# InteractionBoard.net
KiCad netlist of a schematic drawn in EAGLE
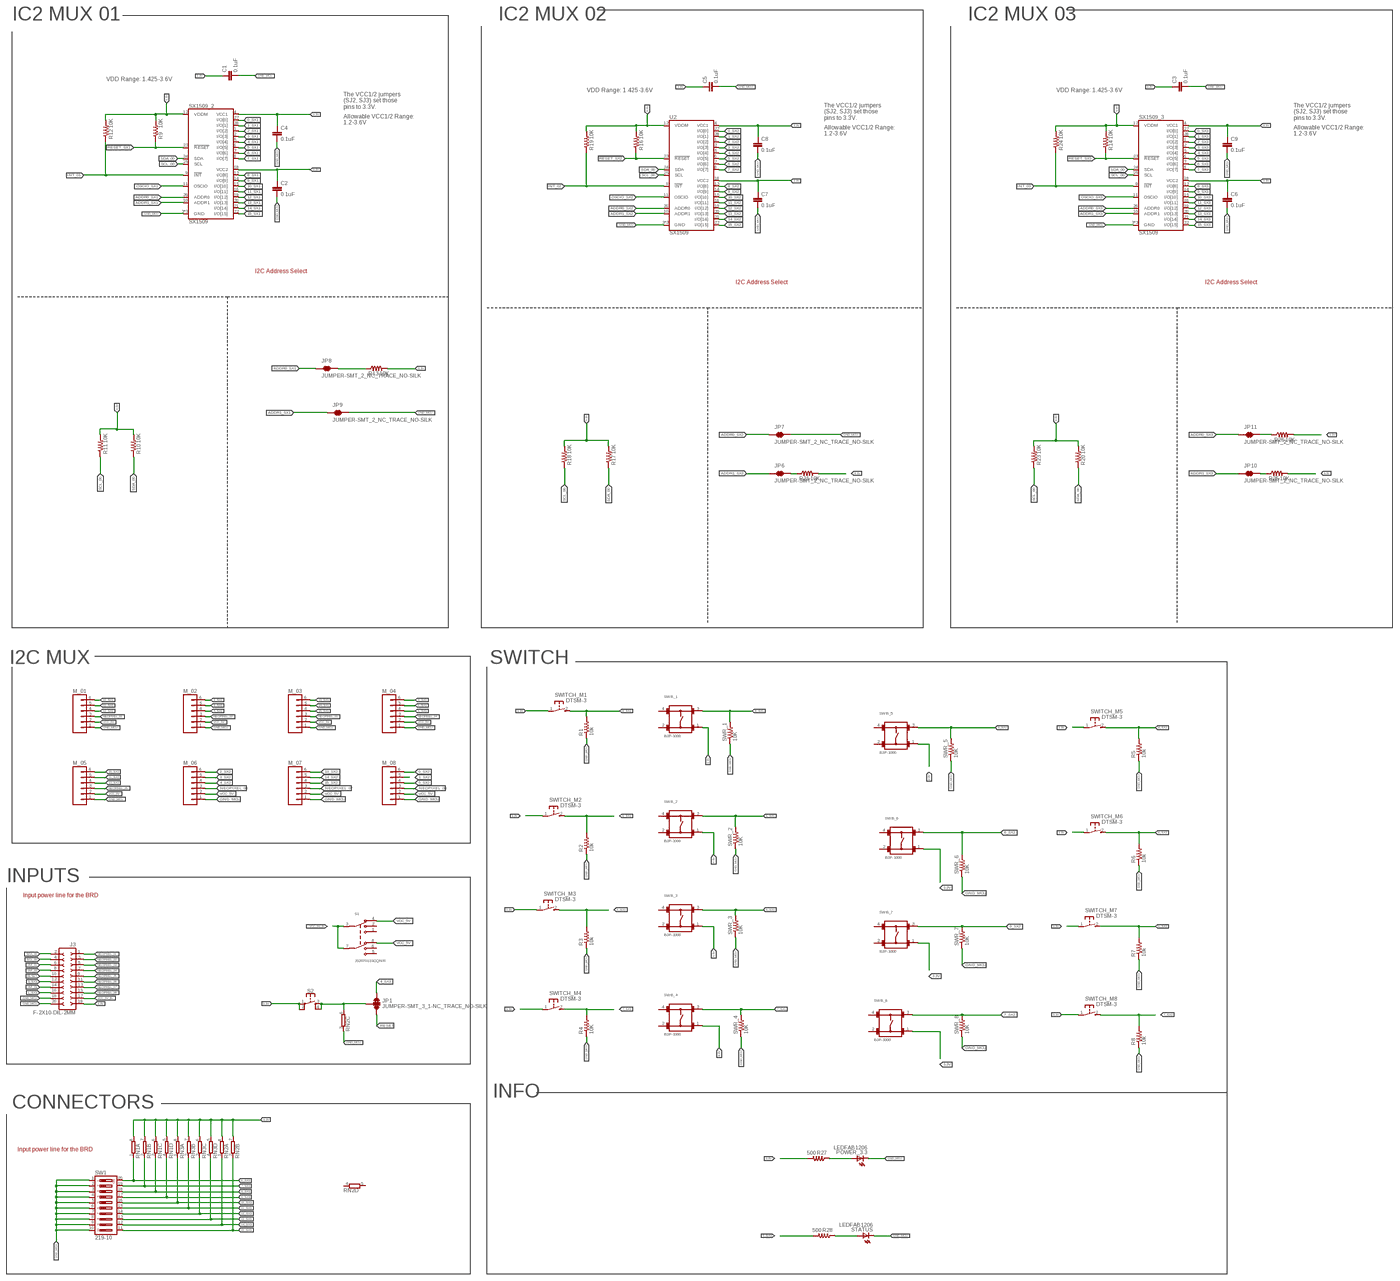
[diagram p0: schematic, sheet 1, overview]
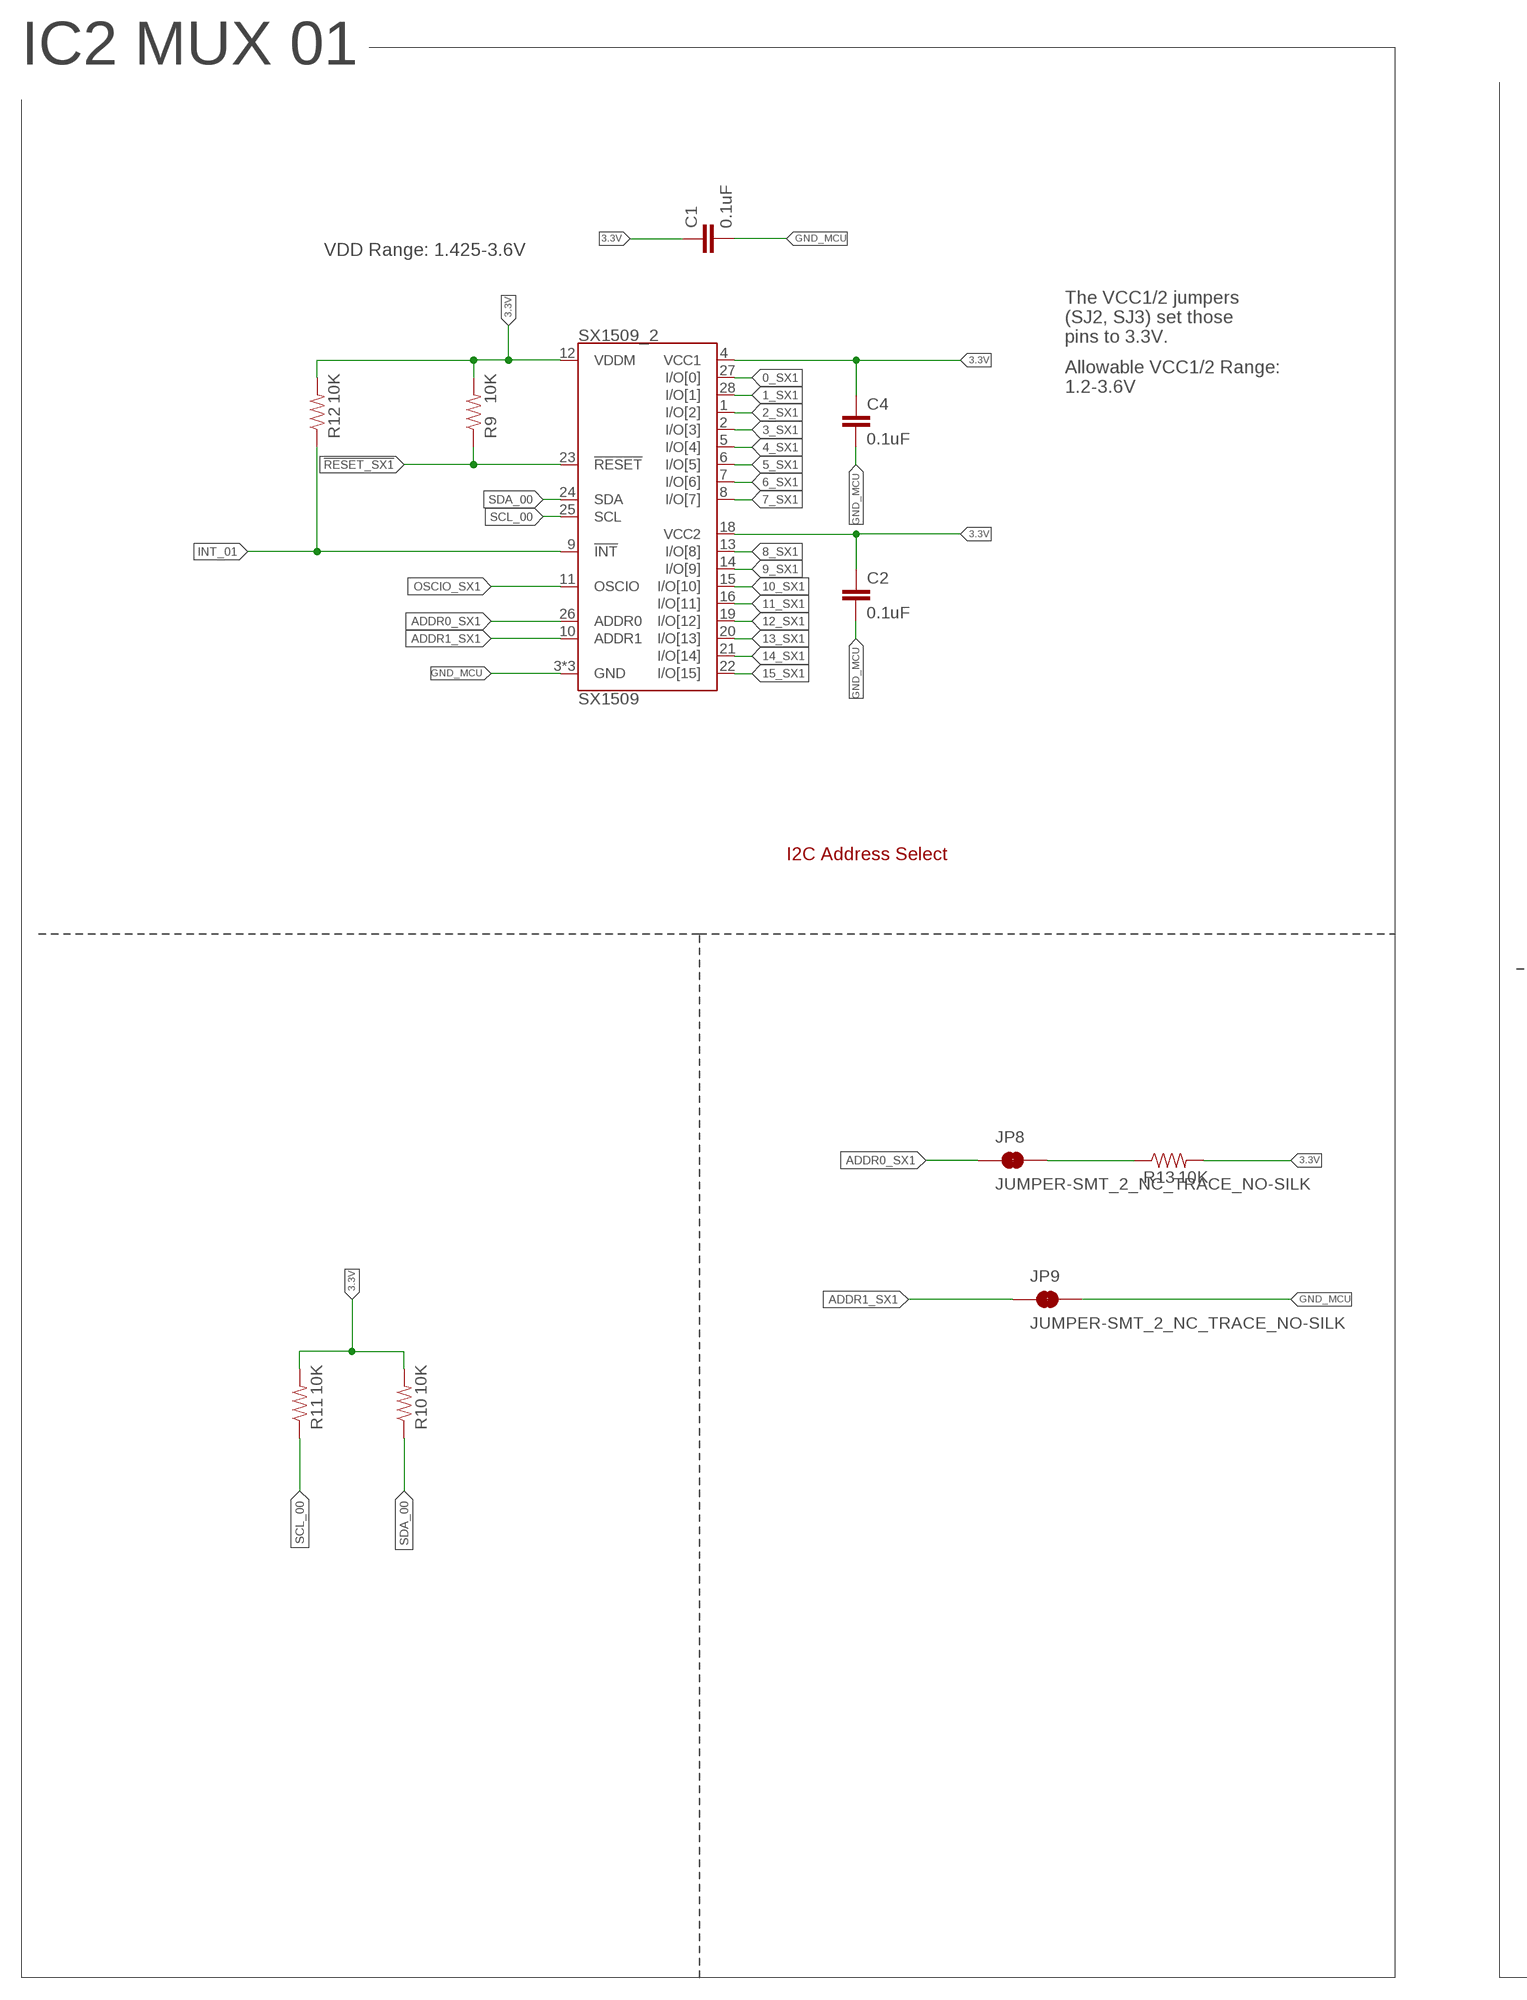
[diagram p1: schematic, sheet 1, part 1 of 4]
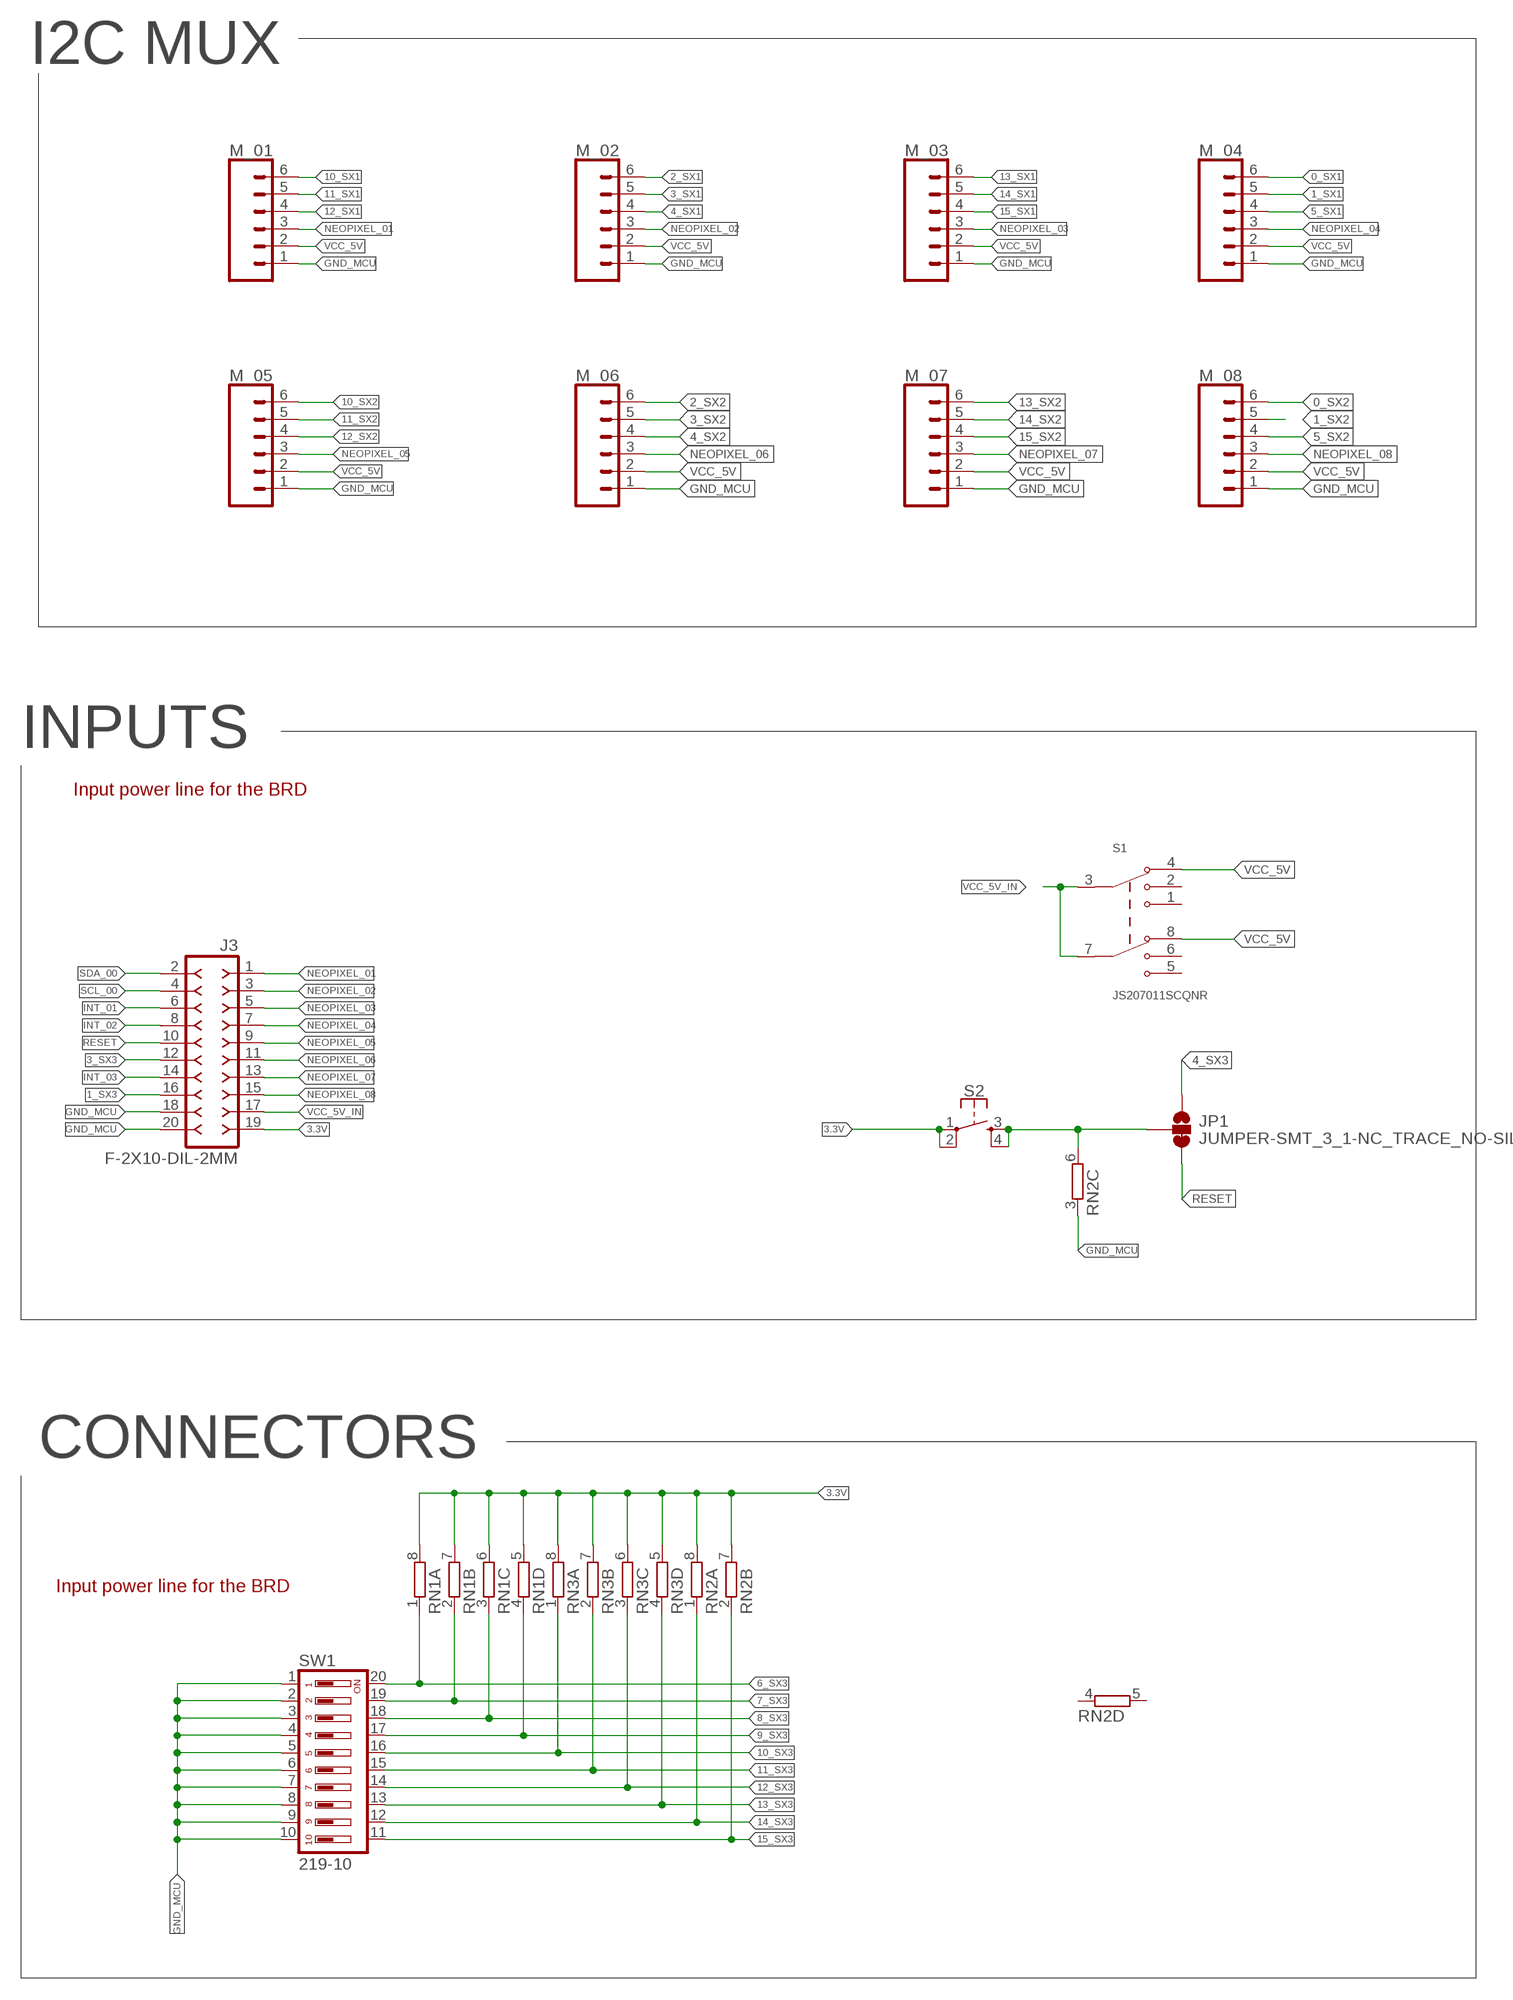
[diagram p2: schematic, sheet 1, part 2 of 4]
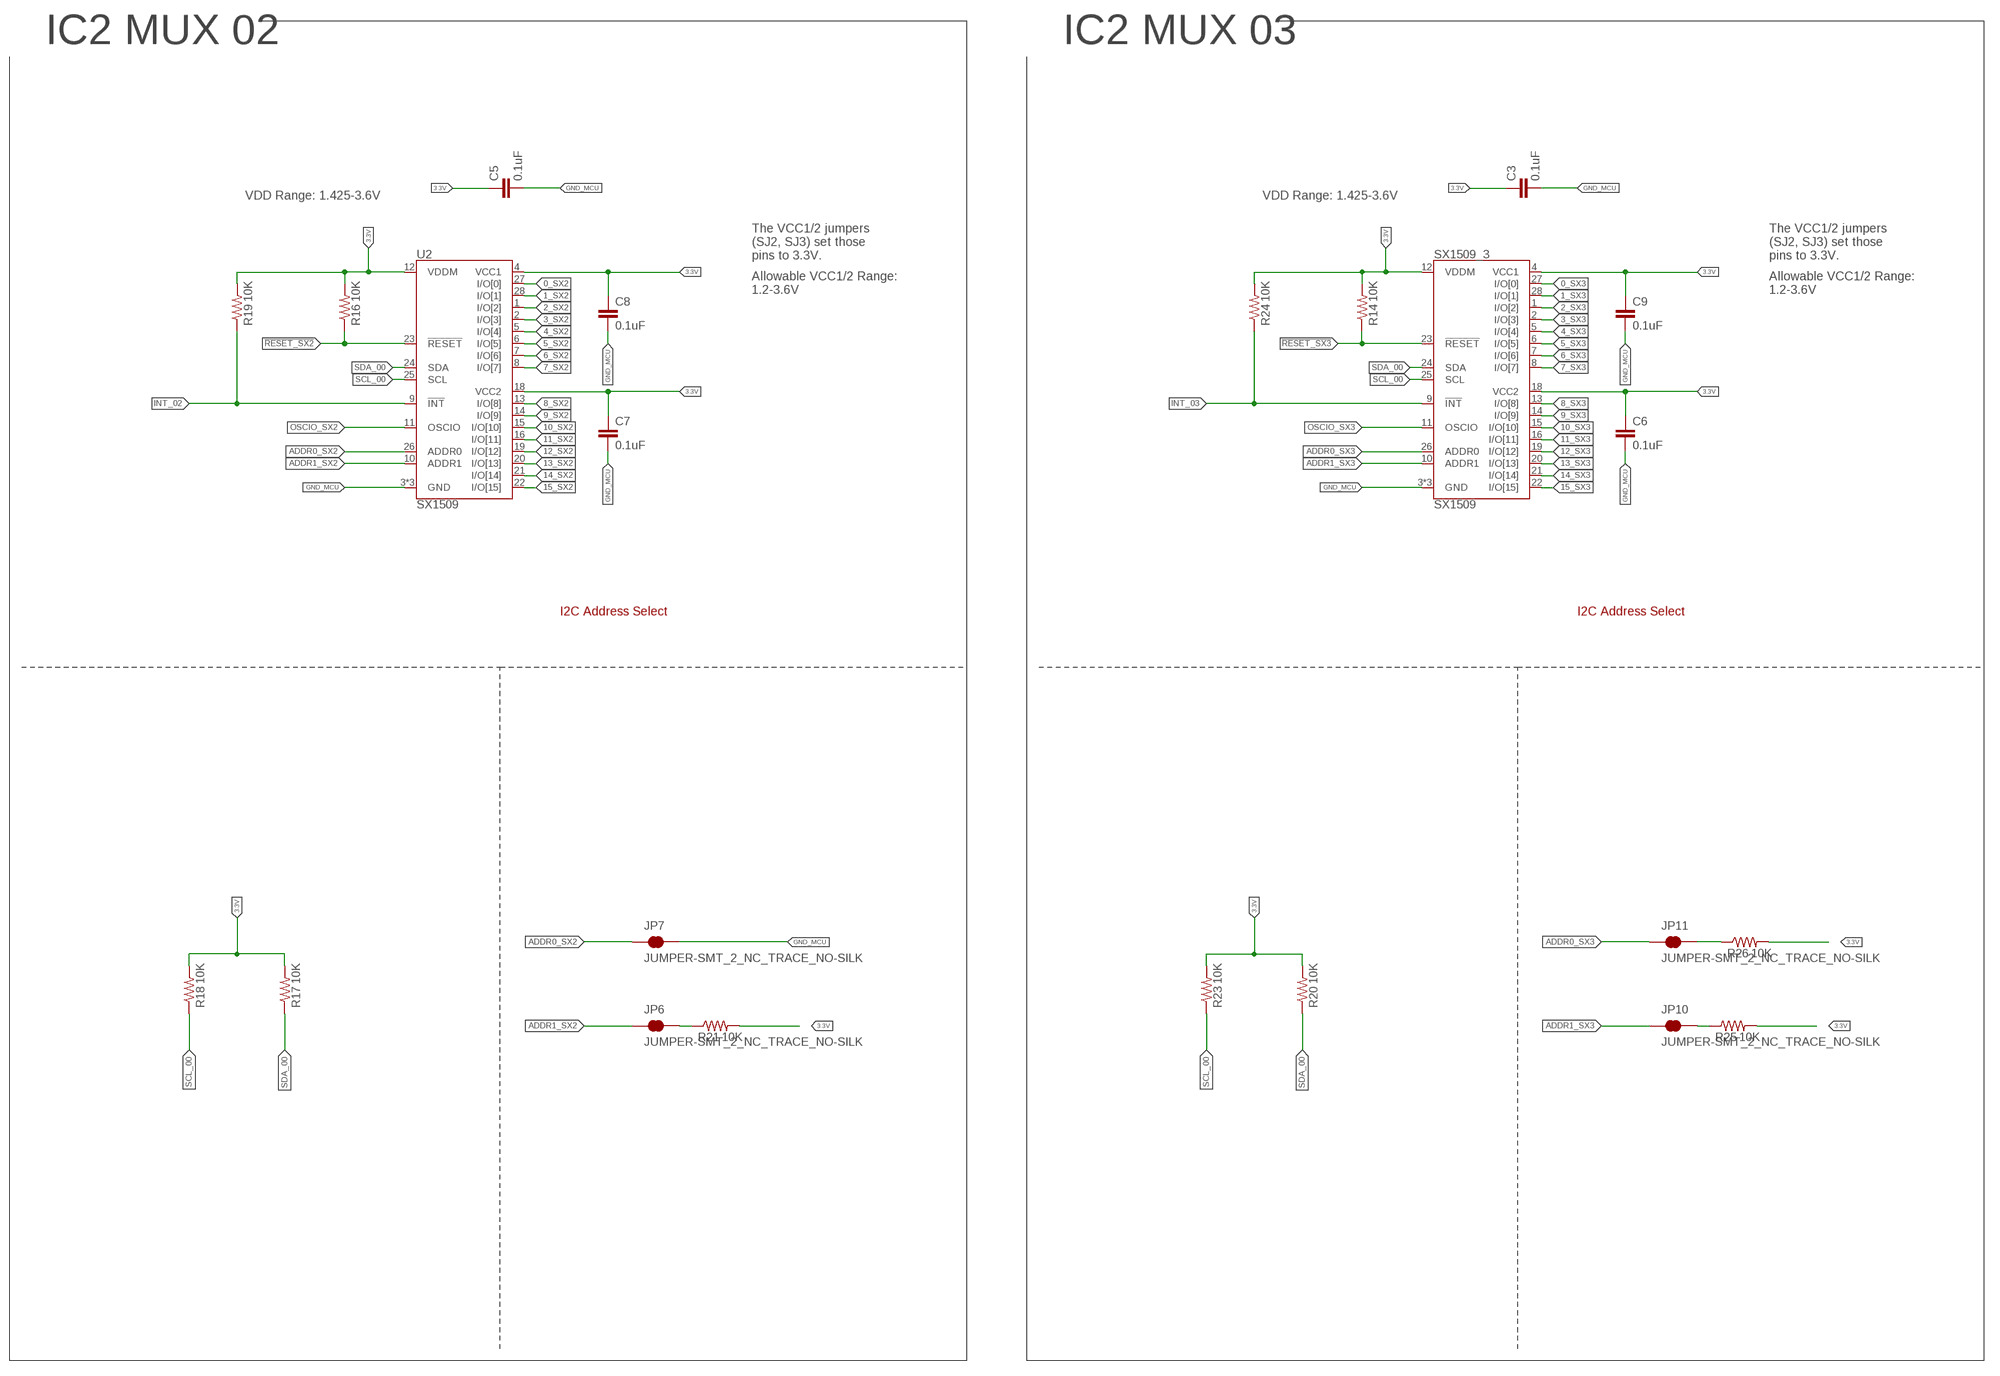
[diagram p3: schematic, sheet 1, part 3 of 4]
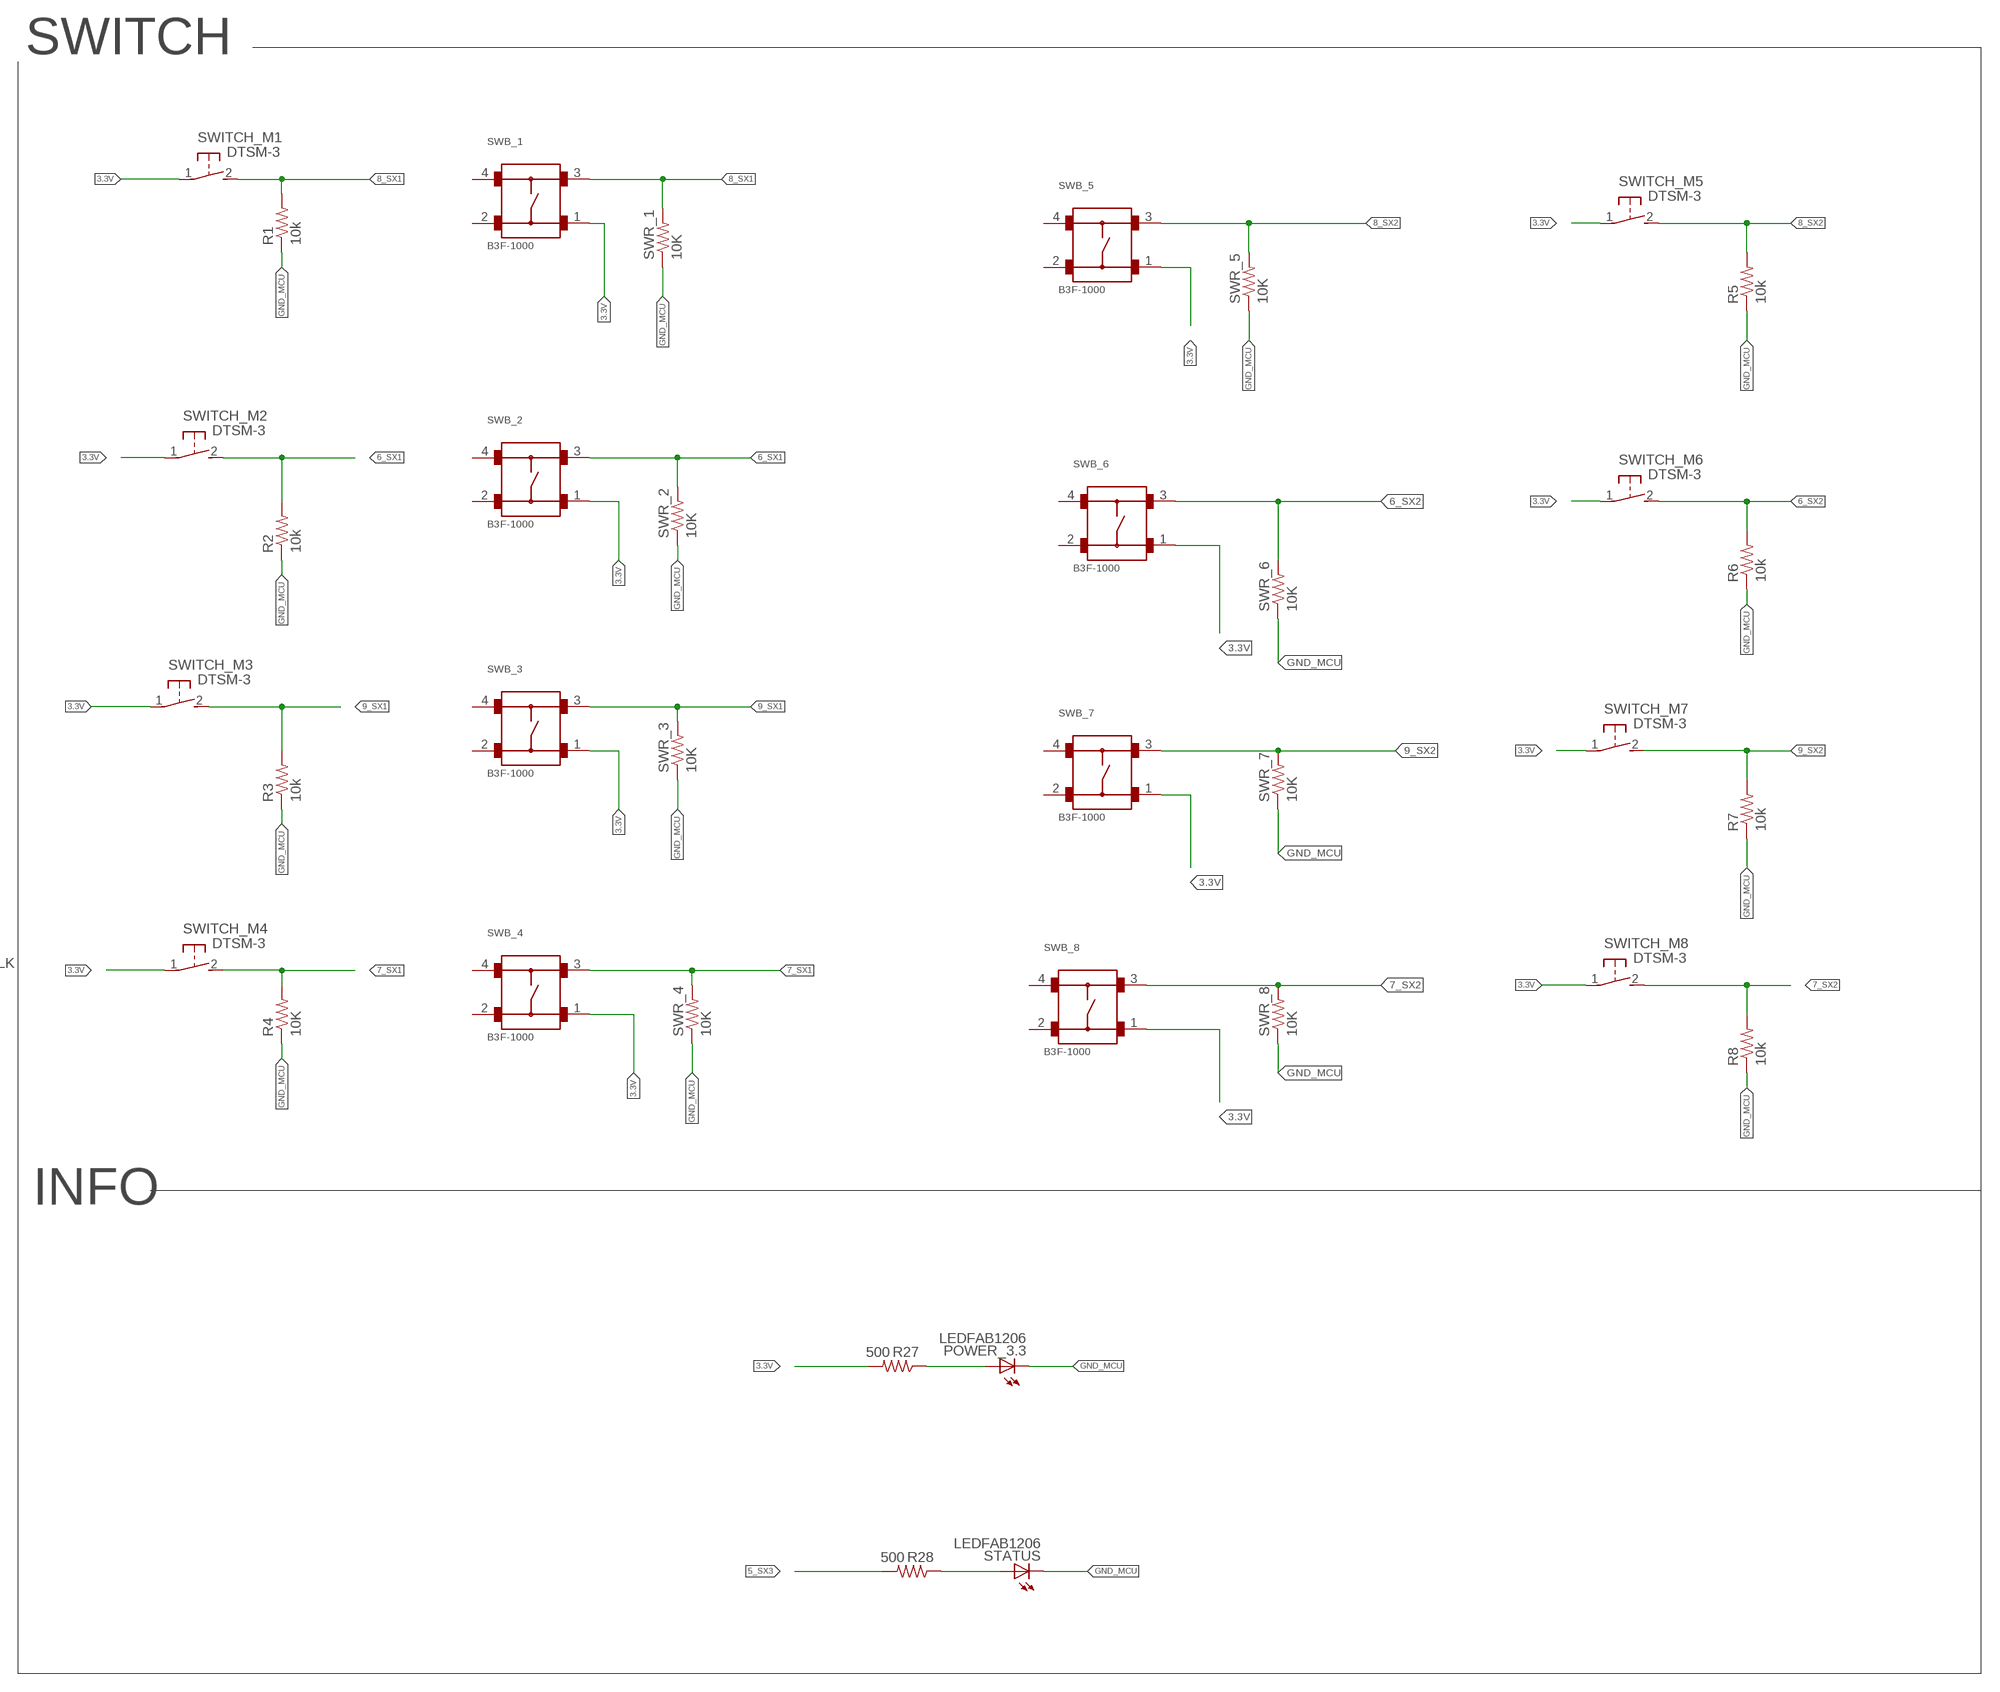
[diagram p4: schematic, sheet 1, part 4 of 4]

(export (version "E")
  (design (tool "Eeschema 10.0.6"))
  (components
    (comp (ref "C1")
      (value "0.1uF")
      (footprint "eagle-import:0603-CAP")
      (libsource (lib "eagle-import") (part "0.1UF-25V(+80/-20%)(0603)"))
    )
    (comp (ref "C2")
      (value "0.1uF")
      (footprint "eagle-import:0603-CAP")
      (libsource (lib "eagle-import") (part "0.1UF-25V(+80/-20%)(0603)"))
    )
    (comp (ref "C3")
      (value "0.1uF")
      (footprint "eagle-import:0603-CAP")
      (libsource (lib "eagle-import") (part "0.1UF-25V(+80/-20%)(0603)"))
    )
    (comp (ref "C4")
      (value "0.1uF")
      (footprint "eagle-import:0603-CAP")
      (libsource (lib "eagle-import") (part "0.1UF-25V(+80/-20%)(0603)"))
    )
    (comp (ref "C5")
      (value "0.1uF")
      (footprint "eagle-import:0603-CAP")
      (libsource (lib "eagle-import") (part "0.1UF-25V(+80/-20%)(0603)"))
    )
    (comp (ref "C6")
      (value "0.1uF")
      (footprint "eagle-import:0603-CAP")
      (libsource (lib "eagle-import") (part "0.1UF-25V(+80/-20%)(0603)"))
    )
    (comp (ref "C7")
      (value "0.1uF")
      (footprint "eagle-import:0603-CAP")
      (libsource (lib "eagle-import") (part "0.1UF-25V(+80/-20%)(0603)"))
    )
    (comp (ref "C8")
      (value "0.1uF")
      (footprint "eagle-import:0603-CAP")
      (libsource (lib "eagle-import") (part "0.1UF-25V(+80/-20%)(0603)"))
    )
    (comp (ref "C9")
      (value "0.1uF")
      (footprint "eagle-import:0603-CAP")
      (libsource (lib "eagle-import") (part "0.1UF-25V(+80/-20%)(0603)"))
    )
    (comp (ref "J3")
      (value "F-2X10-DIL-2MM")
      (footprint "eagle-import:DIL-2MM-2X10")
      (libsource (lib "eagle-import") (part "F-2X10-DIL-2MM"))
    )
    (comp (ref "JP1")
      (value "JUMPER-SMT_3_1-NC_TRACE_NO-SILK")
      (footprint "eagle-import:SMT-JUMPER_3_1-NC_TRACE_NO-SILK")
      (libsource (lib "eagle-import") (part "JUMPER-SMT_3_1-NC_TRACE_NO-SILK"))
    )
    (comp (ref "JP6")
      (value "JUMPER-SMT_2_NC_TRACE_NO-SILK")
      (footprint "eagle-import:SMT-JUMPER_2_NC_TRACE_NO-SILK")
      (libsource (lib "eagle-import") (part "JUMPER-SMT_2_NC_TRACE_NO-SILK"))
    )
    (comp (ref "JP7")
      (value "JUMPER-SMT_2_NC_TRACE_NO-SILK")
      (footprint "eagle-import:SMT-JUMPER_2_NC_TRACE_NO-SILK")
      (libsource (lib "eagle-import") (part "JUMPER-SMT_2_NC_TRACE_NO-SILK"))
    )
    (comp (ref "JP8")
      (value "JUMPER-SMT_2_NC_TRACE_NO-SILK")
      (footprint "eagle-import:SMT-JUMPER_2_NC_TRACE_NO-SILK")
      (libsource (lib "eagle-import") (part "JUMPER-SMT_2_NC_TRACE_NO-SILK"))
    )
    (comp (ref "JP9")
      (value "JUMPER-SMT_2_NC_TRACE_NO-SILK")
      (footprint "eagle-import:SMT-JUMPER_2_NC_TRACE_NO-SILK")
      (libsource (lib "eagle-import") (part "JUMPER-SMT_2_NC_TRACE_NO-SILK"))
    )
    (comp (ref "JP10")
      (value "JUMPER-SMT_2_NC_TRACE_NO-SILK")
      (footprint "eagle-import:SMT-JUMPER_2_NC_TRACE_NO-SILK")
      (libsource (lib "eagle-import") (part "JUMPER-SMT_2_NC_TRACE_NO-SILK"))
    )
    (comp (ref "JP11")
      (value "JUMPER-SMT_2_NC_TRACE_NO-SILK")
      (footprint "eagle-import:SMT-JUMPER_2_NC_TRACE_NO-SILK")
      (libsource (lib "eagle-import") (part "JUMPER-SMT_2_NC_TRACE_NO-SILK"))
    )
    (comp (ref "M_01")
      (value "CONN_06SMD-1MM")
      (footprint "eagle-import:1X06-1MM")
      (libsource (lib "eagle-import") (part "CONN_06SMD-1MM"))
    )
    (comp (ref "M_02")
      (value "CONN_06SMD-1MM")
      (footprint "eagle-import:1X06-1MM")
      (libsource (lib "eagle-import") (part "CONN_06SMD-1MM"))
    )
    (comp (ref "M_03")
      (value "CONN_06SMD-1MM")
      (footprint "eagle-import:1X06-1MM")
      (libsource (lib "eagle-import") (part "CONN_06SMD-1MM"))
    )
    (comp (ref "M_04")
      (value "CONN_06SMD-1MM")
      (footprint "eagle-import:1X06-1MM")
      (libsource (lib "eagle-import") (part "CONN_06SMD-1MM"))
    )
    (comp (ref "M_05")
      (value "CONN_06SMD-1MM")
      (footprint "eagle-import:1X06-1MM")
      (libsource (lib "eagle-import") (part "CONN_06SMD-1MM"))
    )
    (comp (ref "M_06")
      (value "CONN_06SMD-1MM")
      (footprint "eagle-import:1X06-1MM")
      (libsource (lib "eagle-import") (part "CONN_06SMD-1MM"))
    )
    (comp (ref "M_07")
      (value "CONN_06SMD-1MM")
      (footprint "eagle-import:1X06-1MM")
      (libsource (lib "eagle-import") (part "CONN_06SMD-1MM"))
    )
    (comp (ref "M_08")
      (value "CONN_06SMD-1MM")
      (footprint "eagle-import:1X06-1MM")
      (libsource (lib "eagle-import") (part "CONN_06SMD-1MM"))
    )
    (comp (ref "POWER_3.3")
      (value "LEDFAB1206")
      (footprint "eagle-import:LED1206FAB")
      (libsource (lib "eagle-import") (part "LEDFAB1206"))
    )
    (comp (ref "R1")
      (value "10k")
      (footprint "eagle-import:M0805")
      (libsource (lib "eagle-import") (part "R-US_M0805"))
    )
    (comp (ref "R2")
      (value "10k")
      (footprint "eagle-import:M0805")
      (libsource (lib "eagle-import") (part "R-US_M0805"))
    )
    (comp (ref "R3")
      (value "10k")
      (footprint "eagle-import:M0805")
      (libsource (lib "eagle-import") (part "R-US_M0805"))
    )
    (comp (ref "R4")
      (value "10K")
      (footprint "eagle-import:M0805")
      (libsource (lib "eagle-import") (part "R-US_M0805"))
    )
    (comp (ref "R5")
      (value "10k")
      (footprint "eagle-import:M0805")
      (libsource (lib "eagle-import") (part "R-US_M0805"))
    )
    (comp (ref "R6")
      (value "10k")
      (footprint "eagle-import:M0805")
      (libsource (lib "eagle-import") (part "R-US_M0805"))
    )
    (comp (ref "R7")
      (value "10k")
      (footprint "eagle-import:M0805")
      (libsource (lib "eagle-import") (part "R-US_M0805"))
    )
    (comp (ref "R8")
      (value "10k")
      (footprint "eagle-import:M0805")
      (libsource (lib "eagle-import") (part "R-US_M0805"))
    )
    (comp (ref "R9")
      (value "10K")
      (footprint "eagle-import:0603-RES")
      (libsource (lib "eagle-import") (part "SparkFun-Resistors_532_10KOHM-1/10W-1%(0603)0603"))
    )
    (comp (ref "R10")
      (value "10K")
      (footprint "eagle-import:0603-RES")
      (libsource (lib "eagle-import") (part "SparkFun-Resistors_532_10KOHM-1/10W-1%(0603)0603"))
    )
    (comp (ref "R11")
      (value "10K")
      (footprint "eagle-import:0603-RES")
      (libsource (lib "eagle-import") (part "SparkFun-Resistors_532_10KOHM-1/10W-1%(0603)0603"))
    )
    (comp (ref "R12")
      (value "10K")
      (footprint "eagle-import:0603-RES")
      (libsource (lib "eagle-import") (part "SparkFun-Resistors_532_10KOHM-1/10W-1%(0603)0603"))
    )
    (comp (ref "R13")
      (value "10K")
      (footprint "eagle-import:0603-RES")
      (libsource (lib "eagle-import") (part "SparkFun-Resistors_532_10KOHM-1/10W-1%(0603)0603"))
    )
    (comp (ref "R14")
      (value "10K")
      (footprint "eagle-import:0603-RES")
      (libsource (lib "eagle-import") (part "SparkFun-Resistors_532_10KOHM-1/10W-1%(0603)0603"))
    )
    (comp (ref "R16")
      (value "10K")
      (footprint "eagle-import:0603-RES")
      (libsource (lib "eagle-import") (part "SparkFun-Resistors_532_10KOHM-1/10W-1%(0603)0603"))
    )
    (comp (ref "R17")
      (value "10K")
      (footprint "eagle-import:0603-RES")
      (libsource (lib "eagle-import") (part "SparkFun-Resistors_532_10KOHM-1/10W-1%(0603)0603"))
    )
    (comp (ref "R18")
      (value "10K")
      (footprint "eagle-import:0603-RES")
      (libsource (lib "eagle-import") (part "SparkFun-Resistors_532_10KOHM-1/10W-1%(0603)0603"))
    )
    (comp (ref "R19")
      (value "10K")
      (footprint "eagle-import:0603-RES")
      (libsource (lib "eagle-import") (part "SparkFun-Resistors_532_10KOHM-1/10W-1%(0603)0603"))
    )
    (comp (ref "R20")
      (value "10K")
      (footprint "eagle-import:0603-RES")
      (libsource (lib "eagle-import") (part "SparkFun-Resistors_532_10KOHM-1/10W-1%(0603)0603"))
    )
    (comp (ref "R21")
      (value "10K")
      (footprint "eagle-import:0603-RES")
      (libsource (lib "eagle-import") (part "SparkFun-Resistors_532_10KOHM-1/10W-1%(0603)0603"))
    )
    (comp (ref "R23")
      (value "10K")
      (footprint "eagle-import:0603-RES")
      (libsource (lib "eagle-import") (part "SparkFun-Resistors_532_10KOHM-1/10W-1%(0603)0603"))
    )
    (comp (ref "R24")
      (value "10K")
      (footprint "eagle-import:0603-RES")
      (libsource (lib "eagle-import") (part "SparkFun-Resistors_532_10KOHM-1/10W-1%(0603)0603"))
    )
    (comp (ref "R25")
      (value "10K")
      (footprint "eagle-import:0603-RES")
      (libsource (lib "eagle-import") (part "SparkFun-Resistors_532_10KOHM-1/10W-1%(0603)0603"))
    )
    (comp (ref "R26")
      (value "10K")
      (footprint "eagle-import:0603-RES")
      (libsource (lib "eagle-import") (part "SparkFun-Resistors_532_10KOHM-1/10W-1%(0603)0603"))
    )
    (comp (ref "R27")
      (value "500")
      (footprint "eagle-import:0603-RES")
      (libsource (lib "eagle-import") (part "10KOHM-1/10W-1%(0603)0603"))
    )
    (comp (ref "R28")
      (value "500")
      (footprint "eagle-import:0603-RES")
      (libsource (lib "eagle-import") (part "10KOHM-1/10W-1%(0603)0603"))
    )
    (comp (ref "RN1")
      (value "4R-NEXB38V")
      (footprint "eagle-import:EXB38V")
      (libsource (lib "eagle-import") (part "4R-NEXB38V"))
    )
    (comp (ref "RN2")
      (value "4R-NEXB38V")
      (footprint "eagle-import:EXB38V")
      (libsource (lib "eagle-import") (part "4R-NEXB38V"))
    )
    (comp (ref "RN3")
      (value "4R-NEXB38V")
      (footprint "eagle-import:EXB38V")
      (libsource (lib "eagle-import") (part "4R-NEXB38V"))
    )
    (comp (ref "S1")
      (value "JS207011SCQNR")
      (footprint "eagle-import:SW_JS207011SCQNR")
      (fields (field (name "MF") "C&K"))
      (libsource (lib "eagle-import") (part "JS207011SCQNR"))
    )
    (comp (ref "S2")
      (value "MOMENTARY-SWITCH-SPST-2-SMD-5.2MM")
      (footprint "eagle-import:TACTILE_SWITCH_SMD_5.2MM")
      (libsource (lib "eagle-import") (part "MOMENTARY-SWITCH-SPST-2-SMD-5.2MM"))
    )
    (comp (ref "STATUS")
      (value "LEDFAB1206")
      (footprint "eagle-import:LED1206FAB")
      (libsource (lib "eagle-import") (part "LEDFAB1206"))
    )
    (comp (ref "SW1")
      (value "219-10")
      (footprint "eagle-import:CTS-219-10")
      (fields (field (name "MF") "SLI (CML/IDI)") (field (name "MPN") "219-10PK"))
      (libsource (lib "eagle-import") (part "219-10"))
    )
    (comp (ref "SWB_1")
      (value "B3F-1000")
      (footprint "eagle-import:B3F-1000")
      (fields
        (field (name "DIGI_KEY_PART_NUMBER") "SW400-ND")
        (field (name "MANUFACTURER") "Omron Electronics Inc-EMC Div")
        (field (name "CREATED_BY") "PCBLayout.com")
      )
      (libsource (lib "eagle-import") (part "B3F-1000"))
    )
    (comp (ref "SWB_2")
      (value "B3F-1000")
      (footprint "eagle-import:B3F-1000")
      (fields
        (field (name "DIGI_KEY_PART_NUMBER") "SW400-ND")
        (field (name "MANUFACTURER") "Omron Electronics Inc-EMC Div")
        (field (name "CREATED_BY") "PCBLayout.com")
      )
      (libsource (lib "eagle-import") (part "B3F-1000"))
    )
    (comp (ref "SWB_3")
      (value "B3F-1000")
      (footprint "eagle-import:B3F-1000")
      (fields
        (field (name "DIGI_KEY_PART_NUMBER") "SW400-ND")
        (field (name "MANUFACTURER") "Omron Electronics Inc-EMC Div")
        (field (name "CREATED_BY") "PCBLayout.com")
      )
      (libsource (lib "eagle-import") (part "B3F-1000"))
    )
    (comp (ref "SWB_4")
      (value "B3F-1000")
      (footprint "eagle-import:B3F-1000")
      (fields
        (field (name "DIGI_KEY_PART_NUMBER") "SW400-ND")
        (field (name "MANUFACTURER") "Omron Electronics Inc-EMC Div")
        (field (name "CREATED_BY") "PCBLayout.com")
      )
      (libsource (lib "eagle-import") (part "B3F-1000"))
    )
    (comp (ref "SWB_5")
      (value "B3F-1000")
      (footprint "eagle-import:B3F-1000")
      (fields
        (field (name "DIGI_KEY_PART_NUMBER") "SW400-ND")
        (field (name "MANUFACTURER") "Omron Electronics Inc-EMC Div")
        (field (name "CREATED_BY") "PCBLayout.com")
      )
      (libsource (lib "eagle-import") (part "B3F-1000"))
    )
    (comp (ref "SWB_6")
      (value "B3F-1000")
      (footprint "eagle-import:B3F-1000")
      (fields
        (field (name "DIGI_KEY_PART_NUMBER") "SW400-ND")
        (field (name "MANUFACTURER") "Omron Electronics Inc-EMC Div")
        (field (name "CREATED_BY") "PCBLayout.com")
      )
      (libsource (lib "eagle-import") (part "B3F-1000"))
    )
    (comp (ref "SWB_7")
      (value "B3F-1000")
      (footprint "eagle-import:B3F-1000")
      (fields
        (field (name "DIGI_KEY_PART_NUMBER") "SW400-ND")
        (field (name "MANUFACTURER") "Omron Electronics Inc-EMC Div")
        (field (name "CREATED_BY") "PCBLayout.com")
      )
      (libsource (lib "eagle-import") (part "B3F-1000"))
    )
    (comp (ref "SWB_8")
      (value "B3F-1000")
      (footprint "eagle-import:B3F-1000")
      (fields
        (field (name "DIGI_KEY_PART_NUMBER") "SW400-ND")
        (field (name "MANUFACTURER") "Omron Electronics Inc-EMC Div")
        (field (name "CREATED_BY") "PCBLayout.com")
      )
      (libsource (lib "eagle-import") (part "B3F-1000"))
    )
    (comp (ref "SWITCH_M1")
      (value "DTSM-3")
      (footprint "eagle-import:DTSM-3")
      (libsource (lib "eagle-import") (part "DTSM-3"))
    )
    (comp (ref "SWITCH_M2")
      (value "DTSM-3")
      (footprint "eagle-import:DTSM-3")
      (libsource (lib "eagle-import") (part "DTSM-3"))
    )
    (comp (ref "SWITCH_M3")
      (value "DTSM-3")
      (footprint "eagle-import:DTSM-3")
      (libsource (lib "eagle-import") (part "DTSM-3"))
    )
    (comp (ref "SWITCH_M4")
      (value "DTSM-3")
      (footprint "eagle-import:DTSM-3")
      (libsource (lib "eagle-import") (part "DTSM-3"))
    )
    (comp (ref "SWITCH_M5")
      (value "DTSM-3")
      (footprint "eagle-import:DTSM-3")
      (libsource (lib "eagle-import") (part "DTSM-3"))
    )
    (comp (ref "SWITCH_M6")
      (value "DTSM-3")
      (footprint "eagle-import:DTSM-3")
      (libsource (lib "eagle-import") (part "DTSM-3"))
    )
    (comp (ref "SWITCH_M7")
      (value "DTSM-3")
      (footprint "eagle-import:DTSM-3")
      (libsource (lib "eagle-import") (part "DTSM-3"))
    )
    (comp (ref "SWITCH_M8")
      (value "DTSM-3")
      (footprint "eagle-import:DTSM-3")
      (libsource (lib "eagle-import") (part "DTSM-3"))
    )
    (comp (ref "SWR_1")
      (value "10K")
      (footprint "eagle-import:M0805")
      (libsource (lib "eagle-import") (part "R-US_M0805"))
    )
    (comp (ref "SWR_2")
      (value "10K")
      (footprint "eagle-import:M0805")
      (libsource (lib "eagle-import") (part "R-US_M0805"))
    )
    (comp (ref "SWR_3")
      (value "10K")
      (footprint "eagle-import:M0805")
      (libsource (lib "eagle-import") (part "R-US_M0805"))
    )
    (comp (ref "SWR_4")
      (value "10K")
      (footprint "eagle-import:M0805")
      (libsource (lib "eagle-import") (part "R-US_M0805"))
    )
    (comp (ref "SWR_5")
      (value "10K")
      (footprint "eagle-import:M0805")
      (libsource (lib "eagle-import") (part "R-US_M0805"))
    )
    (comp (ref "SWR_6")
      (value "10K")
      (footprint "eagle-import:M0805")
      (libsource (lib "eagle-import") (part "R-US_M0805"))
    )
    (comp (ref "SWR_7")
      (value "10K")
      (footprint "eagle-import:M0805")
      (libsource (lib "eagle-import") (part "R-US_M0805"))
    )
    (comp (ref "SWR_8")
      (value "10K")
      (footprint "eagle-import:M0805")
      (libsource (lib "eagle-import") (part "R-US_M0805"))
    )
    (comp (ref "SX1509_2")
      (value "SX1509")
      (footprint "eagle-import:QFN-28")
      (libsource (lib "eagle-import") (part "SX1509"))
    )
    (comp (ref "SX1509_3")
      (value "SX1509")
      (footprint "eagle-import:QFN-28")
      (libsource (lib "eagle-import") (part "SX1509"))
    )
    (comp (ref "U2")
      (value "SX1509")
      (footprint "eagle-import:QFN-28")
      (libsource (lib "eagle-import") (part "SX1509"))
    )
  )
  (nets
    (net (code "1") (name "/~{RESET_SX1}") (class "Default")
      (node (ref "R9") (pin "1") (pinfunction "1_1") (pintype "passive"))
      (node (ref "SX1509_2") (pin "23") (pinfunction "~{RESET}_23") (pintype "bidirectional"))
    )
    (net (code "2") (name "/~{RESET_SX2}") (class "Default")
      (node (ref "R16") (pin "1") (pinfunction "1_1") (pintype "passive"))
      (node (ref "U2") (pin "23") (pinfunction "~{RESET}_23") (pintype "bidirectional"))
    )
    (net (code "3") (name "/~{RESET_SX3}") (class "Default")
      (node (ref "R14") (pin "1") (pinfunction "1_1") (pintype "passive"))
      (node (ref "SX1509_3") (pin "23") (pinfunction "~{RESET}_23") (pintype "bidirectional"))
    )
    (net (code "4") (name "0_SX1") (class "Default")
      (node (ref "M_04") (pin "6") (pinfunction "6_6") (pintype "passive"))
      (node (ref "SX1509_2") (pin "27") (pinfunction "I/O[0]_27") (pintype "bidirectional"))
    )
    (net (code "5") (name "0_SX2") (class "Default")
      (node (ref "M_08") (pin "6") (pinfunction "6_6") (pintype "passive"))
      (node (ref "U2") (pin "27") (pinfunction "I/O[0]_27") (pintype "bidirectional"))
    )
    (net (code "6") (name "0_SX3") (class "Default")
      (node (ref "SX1509_3") (pin "27") (pinfunction "I/O[0]_27") (pintype "bidirectional"))
    )
    (net (code "7") (name "1_SX1") (class "Default")
      (node (ref "M_04") (pin "5") (pinfunction "5_5") (pintype "passive"))
      (node (ref "SX1509_2") (pin "28") (pinfunction "I/O[1]_28") (pintype "bidirectional"))
    )
    (net (code "8") (name "1_SX2") (class "Default")
      (node (ref "M_08") (pin "5") (pinfunction "5_5") (pintype "passive"))
      (node (ref "U2") (pin "28") (pinfunction "I/O[1]_28") (pintype "bidirectional"))
    )
    (net (code "9") (name "1_SX3") (class "Default")
      (node (ref "J3") (pin "16") (pinfunction "16_16") (pintype "passive"))
      (node (ref "SX1509_3") (pin "28") (pinfunction "I/O[1]_28") (pintype "bidirectional"))
    )
    (net (code "10") (name "2_SX1") (class "Default")
      (node (ref "M_02") (pin "6") (pinfunction "6_6") (pintype "passive"))
      (node (ref "SX1509_2") (pin "1") (pinfunction "I/O[2]_1") (pintype "bidirectional"))
    )
    (net (code "11") (name "2_SX2") (class "Default")
      (node (ref "M_06") (pin "6") (pinfunction "6_6") (pintype "passive"))
      (node (ref "U2") (pin "1") (pinfunction "I/O[2]_1") (pintype "bidirectional"))
    )
    (net (code "12") (name "2_SX3") (class "Default")
      (node (ref "SX1509_3") (pin "1") (pinfunction "I/O[2]_1") (pintype "bidirectional"))
    )
    (net (code "13") (name "3.3V") (class "Default")
      (node (ref "C1") (pin "1") (pinfunction "1_1") (pintype "passive"))
      (node (ref "C2") (pin "1") (pinfunction "1_1") (pintype "passive"))
      (node (ref "C3") (pin "1") (pinfunction "1_1") (pintype "passive"))
      (node (ref "C4") (pin "1") (pinfunction "1_1") (pintype "passive"))
      (node (ref "C5") (pin "1") (pinfunction "1_1") (pintype "passive"))
      (node (ref "C6") (pin "1") (pinfunction "1_1") (pintype "passive"))
      (node (ref "C7") (pin "1") (pinfunction "1_1") (pintype "passive"))
      (node (ref "C8") (pin "1") (pinfunction "1_1") (pintype "passive"))
      (node (ref "C9") (pin "1") (pinfunction "1_1") (pintype "passive"))
      (node (ref "J3") (pin "19") (pinfunction "19_19") (pintype "passive"))
      (node (ref "R10") (pin "2") (pinfunction "2_2") (pintype "passive"))
      (node (ref "R11") (pin "2") (pinfunction "2_2") (pintype "passive"))
      (node (ref "R12") (pin "2") (pinfunction "2_2") (pintype "passive"))
      (node (ref "R13") (pin "2") (pinfunction "2_2") (pintype "passive"))
      (node (ref "R14") (pin "2") (pinfunction "2_2") (pintype "passive"))
      (node (ref "R16") (pin "2") (pinfunction "2_2") (pintype "passive"))
      (node (ref "R17") (pin "2") (pinfunction "2_2") (pintype "passive"))
      (node (ref "R18") (pin "2") (pinfunction "2_2") (pintype "passive"))
      (node (ref "R19") (pin "2") (pinfunction "2_2") (pintype "passive"))
      (node (ref "R20") (pin "2") (pinfunction "2_2") (pintype "passive"))
      (node (ref "R21") (pin "2") (pinfunction "2_2") (pintype "passive"))
      (node (ref "R23") (pin "2") (pinfunction "2_2") (pintype "passive"))
      (node (ref "R24") (pin "2") (pinfunction "2_2") (pintype "passive"))
      (node (ref "R25") (pin "2") (pinfunction "2_2") (pintype "passive"))
      (node (ref "R26") (pin "2") (pinfunction "2_2") (pintype "passive"))
      (node (ref "R27") (pin "2") (pinfunction "2_2") (pintype "passive"))
      (node (ref "R9") (pin "2") (pinfunction "2_2") (pintype "passive"))
      (node (ref "RN1") (pin "5") (pinfunction "2_5") (pintype "passive"))
      (node (ref "RN1") (pin "6") (pinfunction "2_6") (pintype "passive"))
      (node (ref "RN1") (pin "7") (pinfunction "2_7") (pintype "passive"))
      (node (ref "RN1") (pin "8") (pinfunction "2_8") (pintype "passive"))
      (node (ref "RN2") (pin "7") (pinfunction "2_7") (pintype "passive"))
      (node (ref "RN2") (pin "8") (pinfunction "2_8") (pintype "passive"))
      (node (ref "RN3") (pin "5") (pinfunction "2_5") (pintype "passive"))
      (node (ref "RN3") (pin "6") (pinfunction "2_6") (pintype "passive"))
      (node (ref "RN3") (pin "7") (pinfunction "2_7") (pintype "passive"))
      (node (ref "RN3") (pin "8") (pinfunction "2_8") (pintype "passive"))
      (node (ref "S2") (pin "1") (pinfunction "1_1") (pintype "passive"))
      (node (ref "S2") (pin "2") (pinfunction "2_2") (pintype "passive"))
      (node (ref "SWB_1") (pin "1") (pinfunction "1_1") (pintype "passive"))
      (node (ref "SWB_2") (pin "1") (pinfunction "1_1") (pintype "passive"))
      (node (ref "SWB_3") (pin "1") (pinfunction "1_1") (pintype "passive"))
      (node (ref "SWB_4") (pin "1") (pinfunction "1_1") (pintype "passive"))
      (node (ref "SWB_5") (pin "1") (pinfunction "1_1") (pintype "passive"))
      (node (ref "SWB_6") (pin "1") (pinfunction "1_1") (pintype "passive"))
      (node (ref "SWB_7") (pin "1") (pinfunction "1_1") (pintype "passive"))
      (node (ref "SWB_8") (pin "1") (pinfunction "1_1") (pintype "passive"))
      (node (ref "SWITCH_M1") (pin "1") (pinfunction "1_1") (pintype "passive"))
      (node (ref "SWITCH_M2") (pin "1") (pinfunction "1_1") (pintype "passive"))
      (node (ref "SWITCH_M3") (pin "1") (pinfunction "1_1") (pintype "passive"))
      (node (ref "SWITCH_M4") (pin "1") (pinfunction "1_1") (pintype "passive"))
      (node (ref "SWITCH_M5") (pin "1") (pinfunction "1_1") (pintype "passive"))
      (node (ref "SWITCH_M6") (pin "1") (pinfunction "1_1") (pintype "passive"))
      (node (ref "SWITCH_M7") (pin "1") (pinfunction "1_1") (pintype "passive"))
      (node (ref "SWITCH_M8") (pin "1") (pinfunction "1_1") (pintype "passive"))
      (node (ref "SX1509_2") (pin "12") (pinfunction "VDDM_12") (pintype "bidirectional"))
      (node (ref "SX1509_2") (pin "18") (pinfunction "VCC2_18") (pintype "bidirectional"))
      (node (ref "SX1509_2") (pin "4") (pinfunction "VCC1_4") (pintype "bidirectional"))
      (node (ref "SX1509_3") (pin "12") (pinfunction "VDDM_12") (pintype "bidirectional"))
      (node (ref "SX1509_3") (pin "18") (pinfunction "VCC2_18") (pintype "bidirectional"))
      (node (ref "SX1509_3") (pin "4") (pinfunction "VCC1_4") (pintype "bidirectional"))
      (node (ref "U2") (pin "12") (pinfunction "VDDM_12") (pintype "bidirectional"))
      (node (ref "U2") (pin "18") (pinfunction "VCC2_18") (pintype "bidirectional"))
      (node (ref "U2") (pin "4") (pinfunction "VCC1_4") (pintype "bidirectional"))
    )
    (net (code "14") (name "3_SX1") (class "Default")
      (node (ref "M_02") (pin "5") (pinfunction "5_5") (pintype "passive"))
      (node (ref "SX1509_2") (pin "2") (pinfunction "I/O[3]_2") (pintype "bidirectional"))
    )
    (net (code "15") (name "3_SX2") (class "Default")
      (node (ref "M_06") (pin "5") (pinfunction "5_5") (pintype "passive"))
      (node (ref "U2") (pin "2") (pinfunction "I/O[3]_2") (pintype "bidirectional"))
    )
    (net (code "16") (name "3_SX3") (class "Default")
      (node (ref "J3") (pin "12") (pinfunction "12_12") (pintype "passive"))
      (node (ref "SX1509_3") (pin "2") (pinfunction "I/O[3]_2") (pintype "bidirectional"))
    )
    (net (code "17") (name "4_SX1") (class "Default")
      (node (ref "M_02") (pin "4") (pinfunction "4_4") (pintype "passive"))
      (node (ref "SX1509_2") (pin "5") (pinfunction "I/O[4]_5") (pintype "bidirectional"))
    )
    (net (code "18") (name "4_SX2") (class "Default")
      (node (ref "M_06") (pin "4") (pinfunction "4_4") (pintype "passive"))
      (node (ref "U2") (pin "5") (pinfunction "I/O[4]_5") (pintype "bidirectional"))
    )
    (net (code "19") (name "4_SX3") (class "Default")
      (node (ref "JP1") (pin "1") (pinfunction "1_1") (pintype "passive"))
      (node (ref "SX1509_3") (pin "5") (pinfunction "I/O[4]_5") (pintype "bidirectional"))
    )
    (net (code "20") (name "5_SX1") (class "Default")
      (node (ref "M_04") (pin "4") (pinfunction "4_4") (pintype "passive"))
      (node (ref "SX1509_2") (pin "6") (pinfunction "I/O[5]_6") (pintype "bidirectional"))
    )
    (net (code "21") (name "5_SX2") (class "Default")
      (node (ref "M_08") (pin "4") (pinfunction "4_4") (pintype "passive"))
      (node (ref "U2") (pin "6") (pinfunction "I/O[5]_6") (pintype "bidirectional"))
    )
    (net (code "22") (name "5_SX3") (class "Default")
      (node (ref "R28") (pin "2") (pinfunction "2_2") (pintype "passive"))
      (node (ref "SX1509_3") (pin "6") (pinfunction "I/O[5]_6") (pintype "bidirectional"))
    )
    (net (code "23") (name "6_SX1") (class "Default")
      (node (ref "R2") (pin "2") (pinfunction "2_2") (pintype "passive"))
      (node (ref "SWB_2") (pin "3") (pinfunction "3_3") (pintype "passive"))
      (node (ref "SWITCH_M2") (pin "2") (pinfunction "2_2") (pintype "passive"))
      (node (ref "SWR_2") (pin "2") (pinfunction "2_2") (pintype "passive"))
      (node (ref "SX1509_2") (pin "7") (pinfunction "I/O[6]_7") (pintype "bidirectional"))
    )
    (net (code "24") (name "6_SX2") (class "Default")
      (node (ref "R6") (pin "2") (pinfunction "2_2") (pintype "passive"))
      (node (ref "SWB_6") (pin "3") (pinfunction "3_3") (pintype "passive"))
      (node (ref "SWITCH_M6") (pin "2") (pinfunction "2_2") (pintype "passive"))
      (node (ref "SWR_6") (pin "2") (pinfunction "2_2") (pintype "passive"))
      (node (ref "U2") (pin "7") (pinfunction "I/O[6]_7") (pintype "bidirectional"))
    )
    (net (code "25") (name "6_SX3") (class "Default")
      (node (ref "RN1") (pin "1") (pinfunction "1_1") (pintype "passive"))
      (node (ref "SW1") (pin "20") (pinfunction "20_20") (pintype "passive"))
      (node (ref "SX1509_3") (pin "7") (pinfunction "I/O[6]_7") (pintype "bidirectional"))
    )
    (net (code "26") (name "7_SX1") (class "Default")
      (node (ref "R4") (pin "2") (pinfunction "2_2") (pintype "passive"))
      (node (ref "SWB_4") (pin "3") (pinfunction "3_3") (pintype "passive"))
      (node (ref "SWITCH_M4") (pin "2") (pinfunction "2_2") (pintype "passive"))
      (node (ref "SWR_4") (pin "2") (pinfunction "2_2") (pintype "passive"))
      (node (ref "SX1509_2") (pin "8") (pinfunction "I/O[7]_8") (pintype "bidirectional"))
    )
    (net (code "27") (name "7_SX2") (class "Default")
      (node (ref "R8") (pin "2") (pinfunction "2_2") (pintype "passive"))
      (node (ref "SWB_8") (pin "3") (pinfunction "3_3") (pintype "passive"))
      (node (ref "SWITCH_M8") (pin "2") (pinfunction "2_2") (pintype "passive"))
      (node (ref "SWR_8") (pin "2") (pinfunction "2_2") (pintype "passive"))
      (node (ref "U2") (pin "8") (pinfunction "I/O[7]_8") (pintype "bidirectional"))
    )
    (net (code "28") (name "7_SX3") (class "Default")
      (node (ref "RN1") (pin "2") (pinfunction "1_2") (pintype "passive"))
      (node (ref "SW1") (pin "19") (pinfunction "19_19") (pintype "passive"))
      (node (ref "SX1509_3") (pin "8") (pinfunction "I/O[7]_8") (pintype "bidirectional"))
    )
    (net (code "29") (name "8_SX1") (class "Default")
      (node (ref "R1") (pin "2") (pinfunction "2_2") (pintype "passive"))
      (node (ref "SWB_1") (pin "3") (pinfunction "3_3") (pintype "passive"))
      (node (ref "SWITCH_M1") (pin "2") (pinfunction "2_2") (pintype "passive"))
      (node (ref "SWR_1") (pin "2") (pinfunction "2_2") (pintype "passive"))
      (node (ref "SX1509_2") (pin "13") (pinfunction "I/O[8]_13") (pintype "bidirectional"))
    )
    (net (code "30") (name "8_SX2") (class "Default")
      (node (ref "R5") (pin "2") (pinfunction "2_2") (pintype "passive"))
      (node (ref "SWB_5") (pin "3") (pinfunction "3_3") (pintype "passive"))
      (node (ref "SWITCH_M5") (pin "2") (pinfunction "2_2") (pintype "passive"))
      (node (ref "SWR_5") (pin "2") (pinfunction "2_2") (pintype "passive"))
      (node (ref "U2") (pin "13") (pinfunction "I/O[8]_13") (pintype "bidirectional"))
    )
    (net (code "31") (name "8_SX3") (class "Default")
      (node (ref "RN1") (pin "3") (pinfunction "1_3") (pintype "passive"))
      (node (ref "SW1") (pin "18") (pinfunction "18_18") (pintype "passive"))
      (node (ref "SX1509_3") (pin "13") (pinfunction "I/O[8]_13") (pintype "bidirectional"))
    )
    (net (code "32") (name "9_SX1") (class "Default")
      (node (ref "R3") (pin "2") (pinfunction "2_2") (pintype "passive"))
      (node (ref "SWB_3") (pin "3") (pinfunction "3_3") (pintype "passive"))
      (node (ref "SWITCH_M3") (pin "2") (pinfunction "2_2") (pintype "passive"))
      (node (ref "SWR_3") (pin "2") (pinfunction "2_2") (pintype "passive"))
      (node (ref "SX1509_2") (pin "14") (pinfunction "I/O[9]_14") (pintype "bidirectional"))
    )
    (net (code "33") (name "9_SX2") (class "Default")
      (node (ref "R7") (pin "2") (pinfunction "2_2") (pintype "passive"))
      (node (ref "SWB_7") (pin "3") (pinfunction "3_3") (pintype "passive"))
      (node (ref "SWITCH_M7") (pin "2") (pinfunction "2_2") (pintype "passive"))
      (node (ref "SWR_7") (pin "2") (pinfunction "2_2") (pintype "passive"))
      (node (ref "U2") (pin "14") (pinfunction "I/O[9]_14") (pintype "bidirectional"))
    )
    (net (code "34") (name "9_SX3") (class "Default")
      (node (ref "RN1") (pin "4") (pinfunction "1_4") (pintype "passive"))
      (node (ref "SW1") (pin "17") (pinfunction "17_17") (pintype "passive"))
      (node (ref "SX1509_3") (pin "14") (pinfunction "I/O[9]_14") (pintype "bidirectional"))
    )
    (net (code "35") (name "10_SX1") (class "Default")
      (node (ref "M_01") (pin "6") (pinfunction "6_6") (pintype "passive"))
      (node (ref "SX1509_2") (pin "15") (pinfunction "I/O[10]_15") (pintype "bidirectional"))
    )
    (net (code "36") (name "10_SX2") (class "Default")
      (node (ref "M_05") (pin "6") (pinfunction "6_6") (pintype "passive"))
      (node (ref "U2") (pin "15") (pinfunction "I/O[10]_15") (pintype "bidirectional"))
    )
    (net (code "37") (name "10_SX3") (class "Default")
      (node (ref "RN3") (pin "1") (pinfunction "1_1") (pintype "passive"))
      (node (ref "SW1") (pin "16") (pinfunction "16_16") (pintype "passive"))
      (node (ref "SX1509_3") (pin "15") (pinfunction "I/O[10]_15") (pintype "bidirectional"))
    )
    (net (code "38") (name "11_SX1") (class "Default")
      (node (ref "M_01") (pin "5") (pinfunction "5_5") (pintype "passive"))
      (node (ref "SX1509_2") (pin "16") (pinfunction "I/O[11]_16") (pintype "bidirectional"))
    )
    (net (code "39") (name "11_SX2") (class "Default")
      (node (ref "M_05") (pin "5") (pinfunction "5_5") (pintype "passive"))
      (node (ref "U2") (pin "16") (pinfunction "I/O[11]_16") (pintype "bidirectional"))
    )
    (net (code "40") (name "11_SX3") (class "Default")
      (node (ref "RN3") (pin "2") (pinfunction "1_2") (pintype "passive"))
      (node (ref "SW1") (pin "15") (pinfunction "15_15") (pintype "passive"))
      (node (ref "SX1509_3") (pin "16") (pinfunction "I/O[11]_16") (pintype "bidirectional"))
    )
    (net (code "41") (name "12_SX1") (class "Default")
      (node (ref "M_01") (pin "4") (pinfunction "4_4") (pintype "passive"))
      (node (ref "SX1509_2") (pin "19") (pinfunction "I/O[12]_19") (pintype "bidirectional"))
    )
    (net (code "42") (name "12_SX2") (class "Default")
      (node (ref "M_05") (pin "4") (pinfunction "4_4") (pintype "passive"))
      (node (ref "U2") (pin "19") (pinfunction "I/O[12]_19") (pintype "bidirectional"))
    )
    (net (code "43") (name "12_SX3") (class "Default")
      (node (ref "RN3") (pin "3") (pinfunction "1_3") (pintype "passive"))
      (node (ref "SW1") (pin "14") (pinfunction "14_14") (pintype "passive"))
      (node (ref "SX1509_3") (pin "19") (pinfunction "I/O[12]_19") (pintype "bidirectional"))
    )
    (net (code "44") (name "13_SX1") (class "Default")
      (node (ref "M_03") (pin "6") (pinfunction "6_6") (pintype "passive"))
      (node (ref "SX1509_2") (pin "20") (pinfunction "I/O[13]_20") (pintype "bidirectional"))
    )
    (net (code "45") (name "13_SX2") (class "Default")
      (node (ref "M_07") (pin "6") (pinfunction "6_6") (pintype "passive"))
      (node (ref "U2") (pin "20") (pinfunction "I/O[13]_20") (pintype "bidirectional"))
    )
    (net (code "46") (name "13_SX3") (class "Default")
      (node (ref "RN3") (pin "4") (pinfunction "1_4") (pintype "passive"))
      (node (ref "SW1") (pin "13") (pinfunction "13_13") (pintype "passive"))
      (node (ref "SX1509_3") (pin "20") (pinfunction "I/O[13]_20") (pintype "bidirectional"))
    )
    (net (code "47") (name "14_SX1") (class "Default")
      (node (ref "M_03") (pin "5") (pinfunction "5_5") (pintype "passive"))
      (node (ref "SX1509_2") (pin "21") (pinfunction "I/O[14]_21") (pintype "bidirectional"))
    )
    (net (code "48") (name "14_SX2") (class "Default")
      (node (ref "M_07") (pin "5") (pinfunction "5_5") (pintype "passive"))
      (node (ref "U2") (pin "21") (pinfunction "I/O[14]_21") (pintype "bidirectional"))
    )
    (net (code "49") (name "14_SX3") (class "Default")
      (node (ref "RN2") (pin "1") (pinfunction "1_1") (pintype "passive"))
      (node (ref "SW1") (pin "12") (pinfunction "12_12") (pintype "passive"))
      (node (ref "SX1509_3") (pin "21") (pinfunction "I/O[14]_21") (pintype "bidirectional"))
    )
    (net (code "50") (name "15_SX1") (class "Default")
      (node (ref "M_03") (pin "4") (pinfunction "4_4") (pintype "passive"))
      (node (ref "SX1509_2") (pin "22") (pinfunction "I/O[15]_22") (pintype "bidirectional"))
    )
    (net (code "51") (name "15_SX2") (class "Default")
      (node (ref "M_07") (pin "4") (pinfunction "4_4") (pintype "passive"))
      (node (ref "U2") (pin "22") (pinfunction "I/O[15]_22") (pintype "bidirectional"))
    )
    (net (code "52") (name "15_SX3") (class "Default")
      (node (ref "RN2") (pin "2") (pinfunction "1_2") (pintype "passive"))
      (node (ref "SW1") (pin "11") (pinfunction "11_11") (pintype "passive"))
      (node (ref "SX1509_3") (pin "22") (pinfunction "I/O[15]_22") (pintype "bidirectional"))
    )
    (net (code "53") (name "ADDR0_SX1") (class "Default")
      (node (ref "JP8") (pin "1") (pinfunction "1_1") (pintype "passive"))
      (node (ref "SX1509_2") (pin "26") (pinfunction "ADDR0_26") (pintype "bidirectional"))
    )
    (net (code "54") (name "ADDR0_SX2") (class "Default")
      (node (ref "JP7") (pin "1") (pinfunction "1_1") (pintype "passive"))
      (node (ref "U2") (pin "26") (pinfunction "ADDR0_26") (pintype "bidirectional"))
    )
    (net (code "55") (name "ADDR0_SX3") (class "Default")
      (node (ref "JP11") (pin "1") (pinfunction "1_1") (pintype "passive"))
      (node (ref "SX1509_3") (pin "26") (pinfunction "ADDR0_26") (pintype "bidirectional"))
    )
    (net (code "56") (name "ADDR1_SX1") (class "Default")
      (node (ref "JP9") (pin "1") (pinfunction "1_1") (pintype "passive"))
      (node (ref "SX1509_2") (pin "10") (pinfunction "ADDR1_10") (pintype "bidirectional"))
    )
    (net (code "57") (name "ADDR1_SX2") (class "Default")
      (node (ref "JP6") (pin "1") (pinfunction "1_1") (pintype "passive"))
      (node (ref "U2") (pin "10") (pinfunction "ADDR1_10") (pintype "bidirectional"))
    )
    (net (code "58") (name "ADDR1_SX3") (class "Default")
      (node (ref "JP10") (pin "1") (pinfunction "1_1") (pintype "passive"))
      (node (ref "SX1509_3") (pin "10") (pinfunction "ADDR1_10") (pintype "bidirectional"))
    )
    (net (code "59") (name "GND_MCU") (class "Default")
      (node (ref "C1") (pin "2") (pinfunction "2_2") (pintype "passive"))
      (node (ref "C2") (pin "2") (pinfunction "2_2") (pintype "passive"))
      (node (ref "C3") (pin "2") (pinfunction "2_2") (pintype "passive"))
      (node (ref "C4") (pin "2") (pinfunction "2_2") (pintype "passive"))
      (node (ref "C5") (pin "2") (pinfunction "2_2") (pintype "passive"))
      (node (ref "C6") (pin "2") (pinfunction "2_2") (pintype "passive"))
      (node (ref "C7") (pin "2") (pinfunction "2_2") (pintype "passive"))
      (node (ref "C8") (pin "2") (pinfunction "2_2") (pintype "passive"))
      (node (ref "C9") (pin "2") (pinfunction "2_2") (pintype "passive"))
      (node (ref "J3") (pin "18") (pinfunction "18_18") (pintype "passive"))
      (node (ref "J3") (pin "20") (pinfunction "20_20") (pintype "passive"))
      (node (ref "JP7") (pin "2") (pinfunction "2_2") (pintype "passive"))
      (node (ref "JP9") (pin "2") (pinfunction "2_2") (pintype "passive"))
      (node (ref "M_01") (pin "1") (pinfunction "1_1") (pintype "passive"))
      (node (ref "M_02") (pin "1") (pinfunction "1_1") (pintype "passive"))
      (node (ref "M_03") (pin "1") (pinfunction "1_1") (pintype "passive"))
      (node (ref "M_04") (pin "1") (pinfunction "1_1") (pintype "passive"))
      (node (ref "M_05") (pin "1") (pinfunction "1_1") (pintype "passive"))
      (node (ref "M_06") (pin "1") (pinfunction "1_1") (pintype "passive"))
      (node (ref "M_07") (pin "1") (pinfunction "1_1") (pintype "passive"))
      (node (ref "M_08") (pin "1") (pinfunction "1_1") (pintype "passive"))
      (node (ref "POWER_3.3") (pin "2") (pinfunction "C_2") (pintype "passive"))
      (node (ref "R1") (pin "1") (pinfunction "1_1") (pintype "passive"))
      (node (ref "R2") (pin "1") (pinfunction "1_1") (pintype "passive"))
      (node (ref "R3") (pin "1") (pinfunction "1_1") (pintype "passive"))
      (node (ref "R4") (pin "1") (pinfunction "1_1") (pintype "passive"))
      (node (ref "R5") (pin "1") (pinfunction "1_1") (pintype "passive"))
      (node (ref "R6") (pin "1") (pinfunction "1_1") (pintype "passive"))
      (node (ref "R7") (pin "1") (pinfunction "1_1") (pintype "passive"))
      (node (ref "R8") (pin "1") (pinfunction "1_1") (pintype "passive"))
      (node (ref "RN2") (pin "3") (pinfunction "1_3") (pintype "passive"))
      (node (ref "STATUS") (pin "2") (pinfunction "C_2") (pintype "passive"))
      (node (ref "SW1") (pin "1") (pinfunction "1_1") (pintype "passive"))
      (node (ref "SW1") (pin "10") (pinfunction "10_10") (pintype "passive"))
      (node (ref "SW1") (pin "2") (pinfunction "2_2") (pintype "passive"))
      (node (ref "SW1") (pin "3") (pinfunction "3_3") (pintype "passive"))
      (node (ref "SW1") (pin "4") (pinfunction "4_4") (pintype "passive"))
      (node (ref "SW1") (pin "5") (pinfunction "5_5") (pintype "passive"))
      (node (ref "SW1") (pin "6") (pinfunction "6_6") (pintype "passive"))
      (node (ref "SW1") (pin "7") (pinfunction "7_7") (pintype "passive"))
      (node (ref "SW1") (pin "8") (pinfunction "8_8") (pintype "passive"))
      (node (ref "SW1") (pin "9") (pinfunction "9_9") (pintype "passive"))
      (node (ref "SWR_1") (pin "1") (pinfunction "1_1") (pintype "passive"))
      (node (ref "SWR_2") (pin "1") (pinfunction "1_1") (pintype "passive"))
      (node (ref "SWR_3") (pin "1") (pinfunction "1_1") (pintype "passive"))
      (node (ref "SWR_4") (pin "1") (pinfunction "1_1") (pintype "passive"))
      (node (ref "SWR_5") (pin "1") (pinfunction "1_1") (pintype "passive"))
      (node (ref "SWR_6") (pin "1") (pinfunction "1_1") (pintype "passive"))
      (node (ref "SWR_7") (pin "1") (pinfunction "1_1") (pintype "passive"))
      (node (ref "SWR_8") (pin "1") (pinfunction "1_1") (pintype "passive"))
      (node (ref "SX1509_2") (pin "17") (pinfunction "GND_17") (pintype "bidirectional"))
      (node (ref "SX1509_2") (pin "29") (pinfunction "GND_29") (pintype "bidirectional"))
      (node (ref "SX1509_2") (pin "3") (pinfunction "GND_3") (pintype "bidirectional"))
      (node (ref "SX1509_3") (pin "17") (pinfunction "GND_17") (pintype "bidirectional"))
      (node (ref "SX1509_3") (pin "29") (pinfunction "GND_29") (pintype "bidirectional"))
      (node (ref "SX1509_3") (pin "3") (pinfunction "GND_3") (pintype "bidirectional"))
      (node (ref "U2") (pin "17") (pinfunction "GND_17") (pintype "bidirectional"))
      (node (ref "U2") (pin "29") (pinfunction "GND_29") (pintype "bidirectional"))
      (node (ref "U2") (pin "3") (pinfunction "GND_3") (pintype "bidirectional"))
    )
    (net (code "60") (name "INT_01") (class "Default")
      (node (ref "J3") (pin "6") (pinfunction "6_6") (pintype "passive"))
      (node (ref "R12") (pin "1") (pinfunction "1_1") (pintype "passive"))
      (node (ref "SX1509_2") (pin "9") (pinfunction "~{INT}_9") (pintype "bidirectional"))
    )
    (net (code "61") (name "INT_02") (class "Default")
      (node (ref "J3") (pin "8") (pinfunction "8_8") (pintype "passive"))
      (node (ref "R19") (pin "1") (pinfunction "1_1") (pintype "passive"))
      (node (ref "U2") (pin "9") (pinfunction "~{INT}_9") (pintype "bidirectional"))
    )
    (net (code "62") (name "INT_03") (class "Default")
      (node (ref "J3") (pin "14") (pinfunction "14_14") (pintype "passive"))
      (node (ref "R24") (pin "1") (pinfunction "1_1") (pintype "passive"))
      (node (ref "SX1509_3") (pin "9") (pinfunction "~{INT}_9") (pintype "bidirectional"))
    )
    (net (code "63") (name "NEOPIXEL_01") (class "Default")
      (node (ref "J3") (pin "1") (pinfunction "1_1") (pintype "passive"))
      (node (ref "M_01") (pin "3") (pinfunction "3_3") (pintype "passive"))
    )
    (net (code "64") (name "NEOPIXEL_02") (class "Default")
      (node (ref "J3") (pin "3") (pinfunction "3_3") (pintype "passive"))
      (node (ref "M_02") (pin "3") (pinfunction "3_3") (pintype "passive"))
    )
    (net (code "65") (name "NEOPIXEL_03") (class "Default")
      (node (ref "J3") (pin "5") (pinfunction "5_5") (pintype "passive"))
      (node (ref "M_03") (pin "3") (pinfunction "3_3") (pintype "passive"))
    )
    (net (code "66") (name "NEOPIXEL_04") (class "Default")
      (node (ref "J3") (pin "7") (pinfunction "7_7") (pintype "passive"))
      (node (ref "M_04") (pin "3") (pinfunction "3_3") (pintype "passive"))
    )
    (net (code "67") (name "NEOPIXEL_05") (class "Default")
      (node (ref "J3") (pin "9") (pinfunction "9_9") (pintype "passive"))
      (node (ref "M_05") (pin "3") (pinfunction "3_3") (pintype "passive"))
    )
    (net (code "68") (name "NEOPIXEL_06") (class "Default")
      (node (ref "J3") (pin "11") (pinfunction "11_11") (pintype "passive"))
      (node (ref "M_06") (pin "3") (pinfunction "3_3") (pintype "passive"))
    )
    (net (code "69") (name "NEOPIXEL_07") (class "Default")
      (node (ref "J3") (pin "13") (pinfunction "13_13") (pintype "passive"))
      (node (ref "M_07") (pin "3") (pinfunction "3_3") (pintype "passive"))
    )
    (net (code "70") (name "NEOPIXEL_08") (class "Default")
      (node (ref "J3") (pin "15") (pinfunction "15_15") (pintype "passive"))
      (node (ref "M_08") (pin "3") (pinfunction "3_3") (pintype "passive"))
    )
    (net (code "71") (name "Net-(JP6-Pad2)") (class "Default")
      (node (ref "JP6") (pin "2") (pinfunction "2_2") (pintype "passive"))
      (node (ref "R21") (pin "1") (pinfunction "1_1") (pintype "passive"))
    )
    (net (code "72") (name "Net-(JP8-Pad2)") (class "Default")
      (node (ref "JP8") (pin "2") (pinfunction "2_2") (pintype "passive"))
      (node (ref "R13") (pin "1") (pinfunction "1_1") (pintype "passive"))
    )
    (net (code "73") (name "Net-(JP10-Pad2)") (class "Default")
      (node (ref "JP10") (pin "2") (pinfunction "2_2") (pintype "passive"))
      (node (ref "R25") (pin "1") (pinfunction "1_1") (pintype "passive"))
    )
    (net (code "74") (name "Net-(JP11-Pad2)") (class "Default")
      (node (ref "JP11") (pin "2") (pinfunction "2_2") (pintype "passive"))
      (node (ref "R26") (pin "1") (pinfunction "1_1") (pintype "passive"))
    )
    (net (code "75") (name "Net-(POWER_3.3-A)") (class "Default")
      (node (ref "POWER_3.3") (pin "1") (pinfunction "A_1") (pintype "passive"))
      (node (ref "R27") (pin "1") (pinfunction "1_1") (pintype "passive"))
    )
    (net (code "76") (name "Net-(STATUS-A)") (class "Default")
      (node (ref "R28") (pin "1") (pinfunction "1_1") (pintype "passive"))
      (node (ref "STATUS") (pin "1") (pinfunction "A_1") (pintype "passive"))
    )
    (net (code "77") (name "OSCIO_SX1") (class "Default")
      (node (ref "SX1509_2") (pin "11") (pinfunction "OSCIO_11") (pintype "bidirectional"))
    )
    (net (code "78") (name "OSCIO_SX2") (class "Default")
      (node (ref "U2") (pin "11") (pinfunction "OSCIO_11") (pintype "bidirectional"))
    )
    (net (code "79") (name "OSCIO_SX3") (class "Default")
      (node (ref "SX1509_3") (pin "11") (pinfunction "OSCIO_11") (pintype "bidirectional"))
    )
    (net (code "80") (name "RESET") (class "Default")
      (node (ref "J3") (pin "10") (pinfunction "10_10") (pintype "passive"))
      (node (ref "JP1") (pin "2") (pinfunction "2_2") (pintype "passive"))
      (node (ref "JP1") (pin "3") (pinfunction "3_3") (pintype "passive"))
      (node (ref "RN2") (pin "6") (pinfunction "2_6") (pintype "passive"))
      (node (ref "S2") (pin "3") (pinfunction "3_3") (pintype "passive"))
      (node (ref "S2") (pin "4") (pinfunction "4_4") (pintype "passive"))
    )
    (net (code "81") (name "SCL_00") (class "Default")
      (node (ref "J3") (pin "4") (pinfunction "4_4") (pintype "passive"))
      (node (ref "R11") (pin "1") (pinfunction "1_1") (pintype "passive"))
      (node (ref "R18") (pin "1") (pinfunction "1_1") (pintype "passive"))
      (node (ref "R23") (pin "1") (pinfunction "1_1") (pintype "passive"))
      (node (ref "SX1509_2") (pin "25") (pinfunction "SCL_25") (pintype "bidirectional"))
      (node (ref "SX1509_3") (pin "25") (pinfunction "SCL_25") (pintype "bidirectional"))
      (node (ref "U2") (pin "25") (pinfunction "SCL_25") (pintype "bidirectional"))
    )
    (net (code "82") (name "SDA_00") (class "Default")
      (node (ref "J3") (pin "2") (pinfunction "2_2") (pintype "passive"))
      (node (ref "R10") (pin "1") (pinfunction "1_1") (pintype "passive"))
      (node (ref "R17") (pin "1") (pinfunction "1_1") (pintype "passive"))
      (node (ref "R20") (pin "1") (pinfunction "1_1") (pintype "passive"))
      (node (ref "SX1509_2") (pin "24") (pinfunction "SDA_24") (pintype "bidirectional"))
      (node (ref "SX1509_3") (pin "24") (pinfunction "SDA_24") (pintype "bidirectional"))
      (node (ref "U2") (pin "24") (pinfunction "SDA_24") (pintype "bidirectional"))
    )
    (net (code "83") (name "VCC_5V") (class "Default")
      (node (ref "M_01") (pin "2") (pinfunction "2_2") (pintype "passive"))
      (node (ref "M_02") (pin "2") (pinfunction "2_2") (pintype "passive"))
      (node (ref "M_03") (pin "2") (pinfunction "2_2") (pintype "passive"))
      (node (ref "M_04") (pin "2") (pinfunction "2_2") (pintype "passive"))
      (node (ref "M_05") (pin "2") (pinfunction "2_2") (pintype "passive"))
      (node (ref "M_06") (pin "2") (pinfunction "2_2") (pintype "passive"))
      (node (ref "M_07") (pin "2") (pinfunction "2_2") (pintype "passive"))
      (node (ref "M_08") (pin "2") (pinfunction "2_2") (pintype "passive"))
      (node (ref "S1") (pin "4") (pinfunction "4_4") (pintype "passive"))
      (node (ref "S1") (pin "8") (pinfunction "8_8") (pintype "passive"))
    )
    (net (code "84") (name "VCC_5V_IN") (class "Default")
      (node (ref "J3") (pin "17") (pinfunction "17_17") (pintype "passive"))
      (node (ref "S1") (pin "3") (pinfunction "3_3") (pintype "passive"))
      (node (ref "S1") (pin "7") (pinfunction "7_7") (pintype "passive"))
    )
    (net (code "85") (name "unconnected-(RN2D-1-Pad4)") (class "Default")
      (node (ref "RN2") (pin "4") (pinfunction "1_4") (pintype "passive"))
    )
    (net (code "86") (name "unconnected-(RN2D-2-Pad5)") (class "Default")
      (node (ref "RN2") (pin "5") (pinfunction "2_5") (pintype "passive"))
    )
    (net (code "87") (name "unconnected-(S1-Pad1)") (class "Default")
      (node (ref "S1") (pin "1") (pinfunction "1_1") (pintype "passive"))
    )
    (net (code "88") (name "unconnected-(S1-Pad2)") (class "Default")
      (node (ref "S1") (pin "2") (pinfunction "2_2") (pintype "passive"))
    )
    (net (code "89") (name "unconnected-(S1-Pad5)") (class "Default")
      (node (ref "S1") (pin "5") (pinfunction "5_5") (pintype "passive"))
    )
    (net (code "90") (name "unconnected-(S1-Pad6)") (class "Default")
      (node (ref "S1") (pin "6") (pinfunction "6_6") (pintype "passive"))
    )
    (net (code "91") (name "unconnected-(SWB_1-Pad2)") (class "Default")
      (node (ref "SWB_1") (pin "2") (pinfunction "2_2") (pintype "passive"))
    )
    (net (code "92") (name "unconnected-(SWB_1-Pad4)") (class "Default")
      (node (ref "SWB_1") (pin "4") (pinfunction "4_4") (pintype "passive"))
    )
    (net (code "93") (name "unconnected-(SWB_2-Pad2)") (class "Default")
      (node (ref "SWB_2") (pin "2") (pinfunction "2_2") (pintype "passive"))
    )
    (net (code "94") (name "unconnected-(SWB_2-Pad4)") (class "Default")
      (node (ref "SWB_2") (pin "4") (pinfunction "4_4") (pintype "passive"))
    )
    (net (code "95") (name "unconnected-(SWB_3-Pad2)") (class "Default")
      (node (ref "SWB_3") (pin "2") (pinfunction "2_2") (pintype "passive"))
    )
    (net (code "96") (name "unconnected-(SWB_3-Pad4)") (class "Default")
      (node (ref "SWB_3") (pin "4") (pinfunction "4_4") (pintype "passive"))
    )
    (net (code "97") (name "unconnected-(SWB_4-Pad2)") (class "Default")
      (node (ref "SWB_4") (pin "2") (pinfunction "2_2") (pintype "passive"))
    )
    (net (code "98") (name "unconnected-(SWB_4-Pad4)") (class "Default")
      (node (ref "SWB_4") (pin "4") (pinfunction "4_4") (pintype "passive"))
    )
    (net (code "99") (name "unconnected-(SWB_5-Pad2)") (class "Default")
      (node (ref "SWB_5") (pin "2") (pinfunction "2_2") (pintype "passive"))
    )
    (net (code "100") (name "unconnected-(SWB_5-Pad4)") (class "Default")
      (node (ref "SWB_5") (pin "4") (pinfunction "4_4") (pintype "passive"))
    )
    (net (code "101") (name "unconnected-(SWB_6-Pad2)") (class "Default")
      (node (ref "SWB_6") (pin "2") (pinfunction "2_2") (pintype "passive"))
    )
    (net (code "102") (name "unconnected-(SWB_6-Pad4)") (class "Default")
      (node (ref "SWB_6") (pin "4") (pinfunction "4_4") (pintype "passive"))
    )
    (net (code "103") (name "unconnected-(SWB_7-Pad2)") (class "Default")
      (node (ref "SWB_7") (pin "2") (pinfunction "2_2") (pintype "passive"))
    )
    (net (code "104") (name "unconnected-(SWB_7-Pad4)") (class "Default")
      (node (ref "SWB_7") (pin "4") (pinfunction "4_4") (pintype "passive"))
    )
    (net (code "105") (name "unconnected-(SWB_8-Pad2)") (class "Default")
      (node (ref "SWB_8") (pin "2") (pinfunction "2_2") (pintype "passive"))
    )
    (net (code "106") (name "unconnected-(SWB_8-Pad4)") (class "Default")
      (node (ref "SWB_8") (pin "4") (pinfunction "4_4") (pintype "passive"))
    )
  )
)
